# 12ChannelEMG.net
KiCad netlist of a schematic drawn in EAGLE
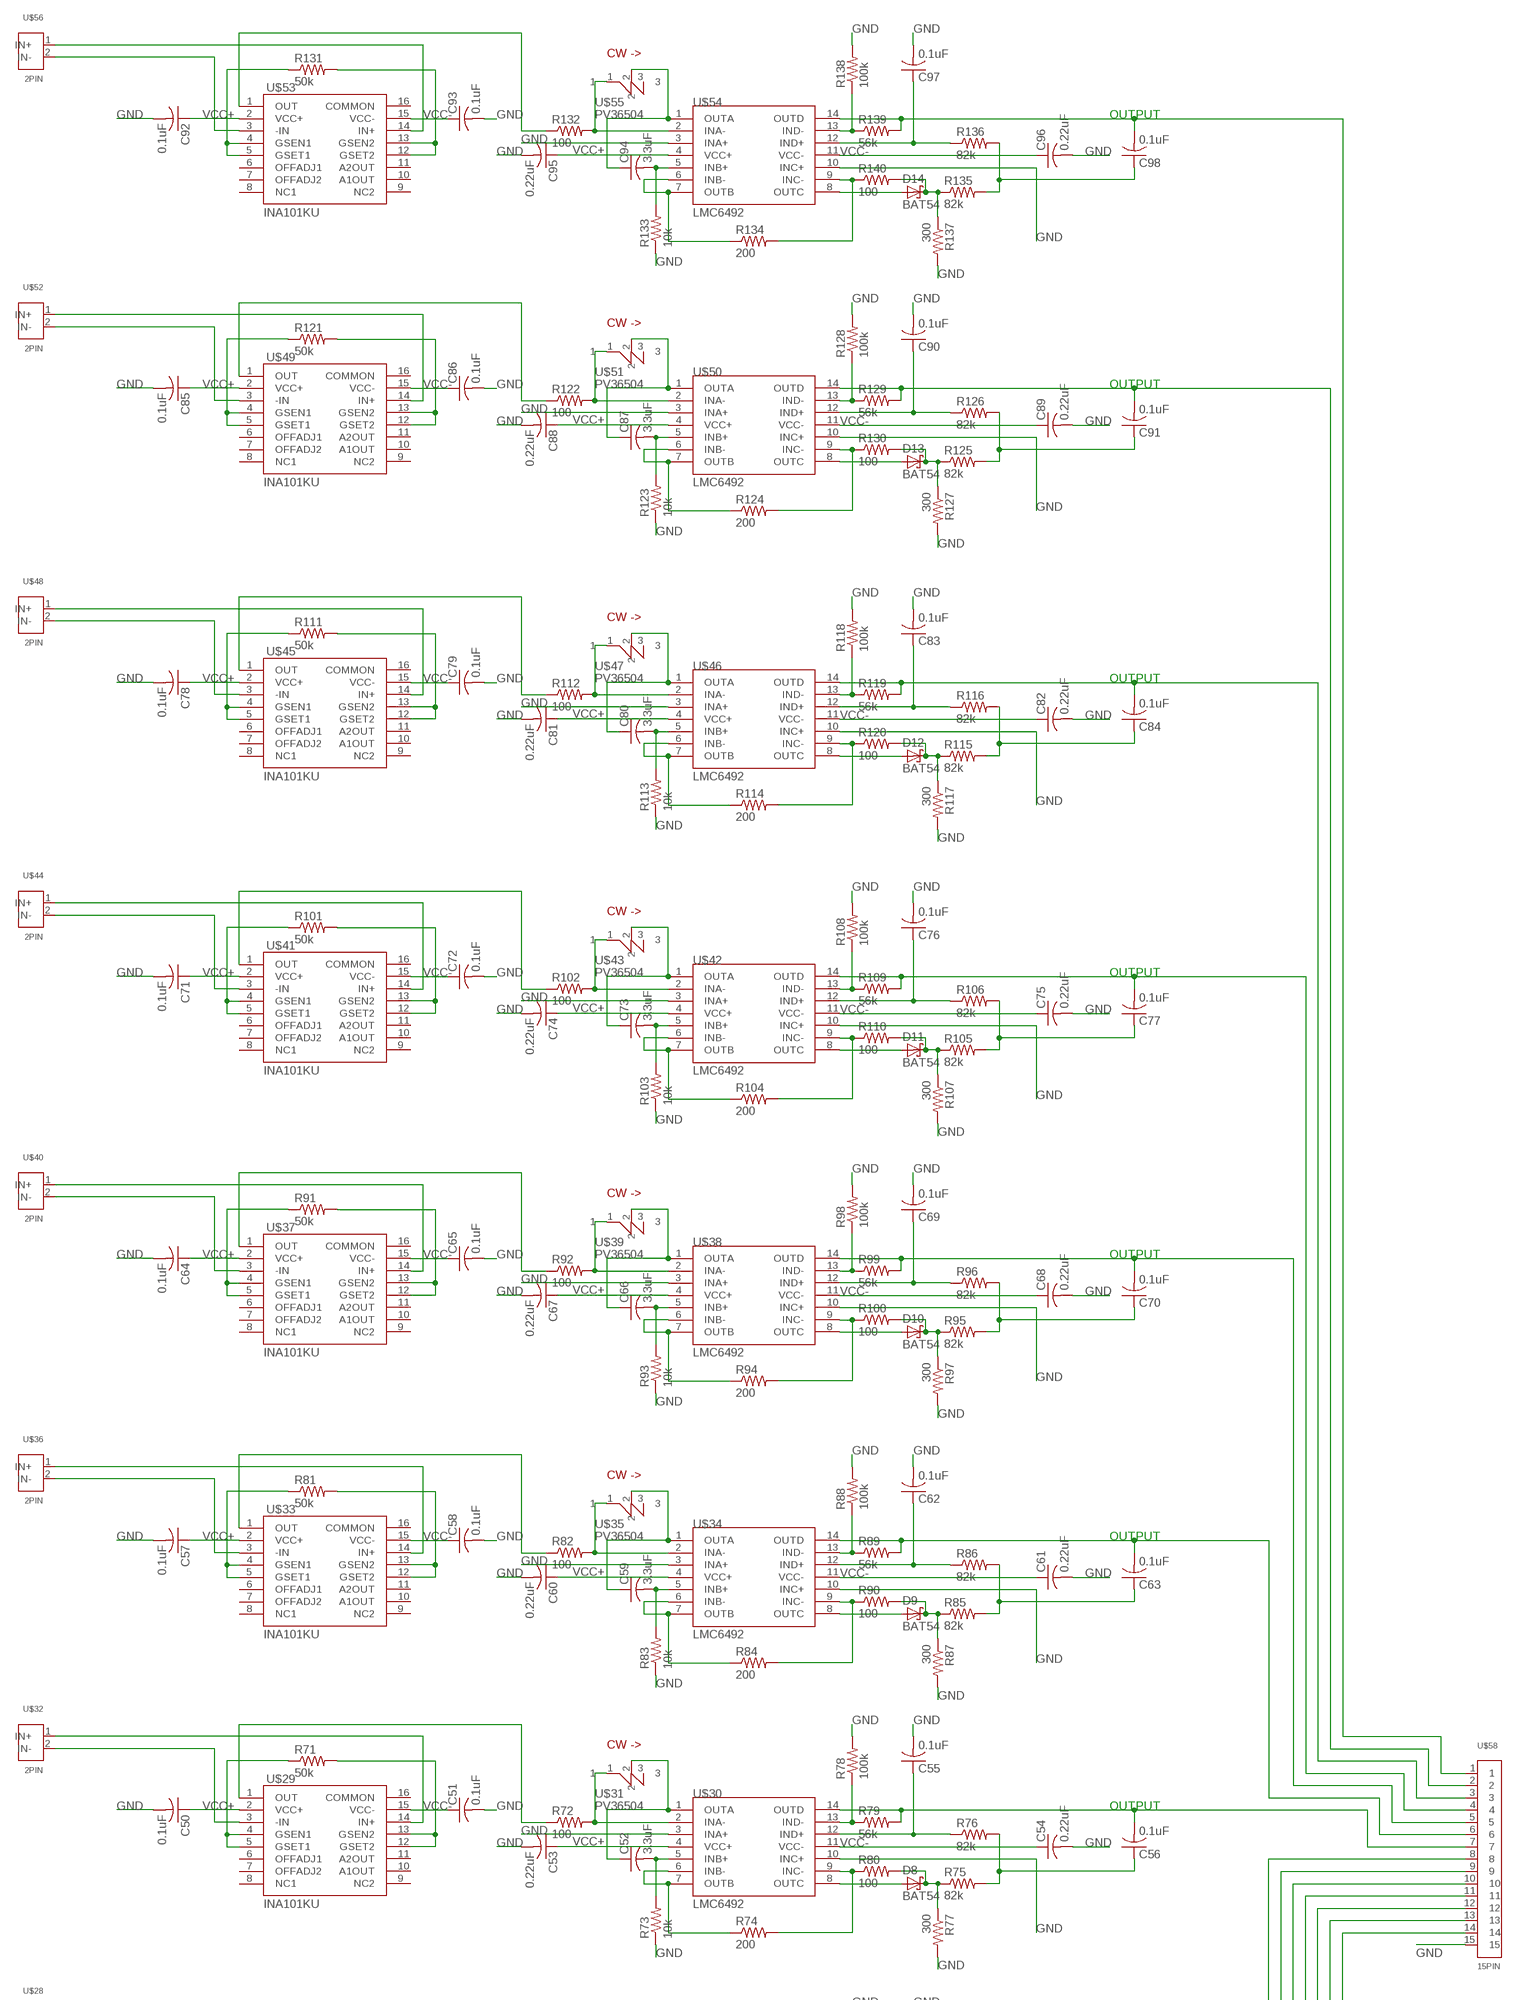
[diagram p0: schematic, sheet 1, part 1 of 2]
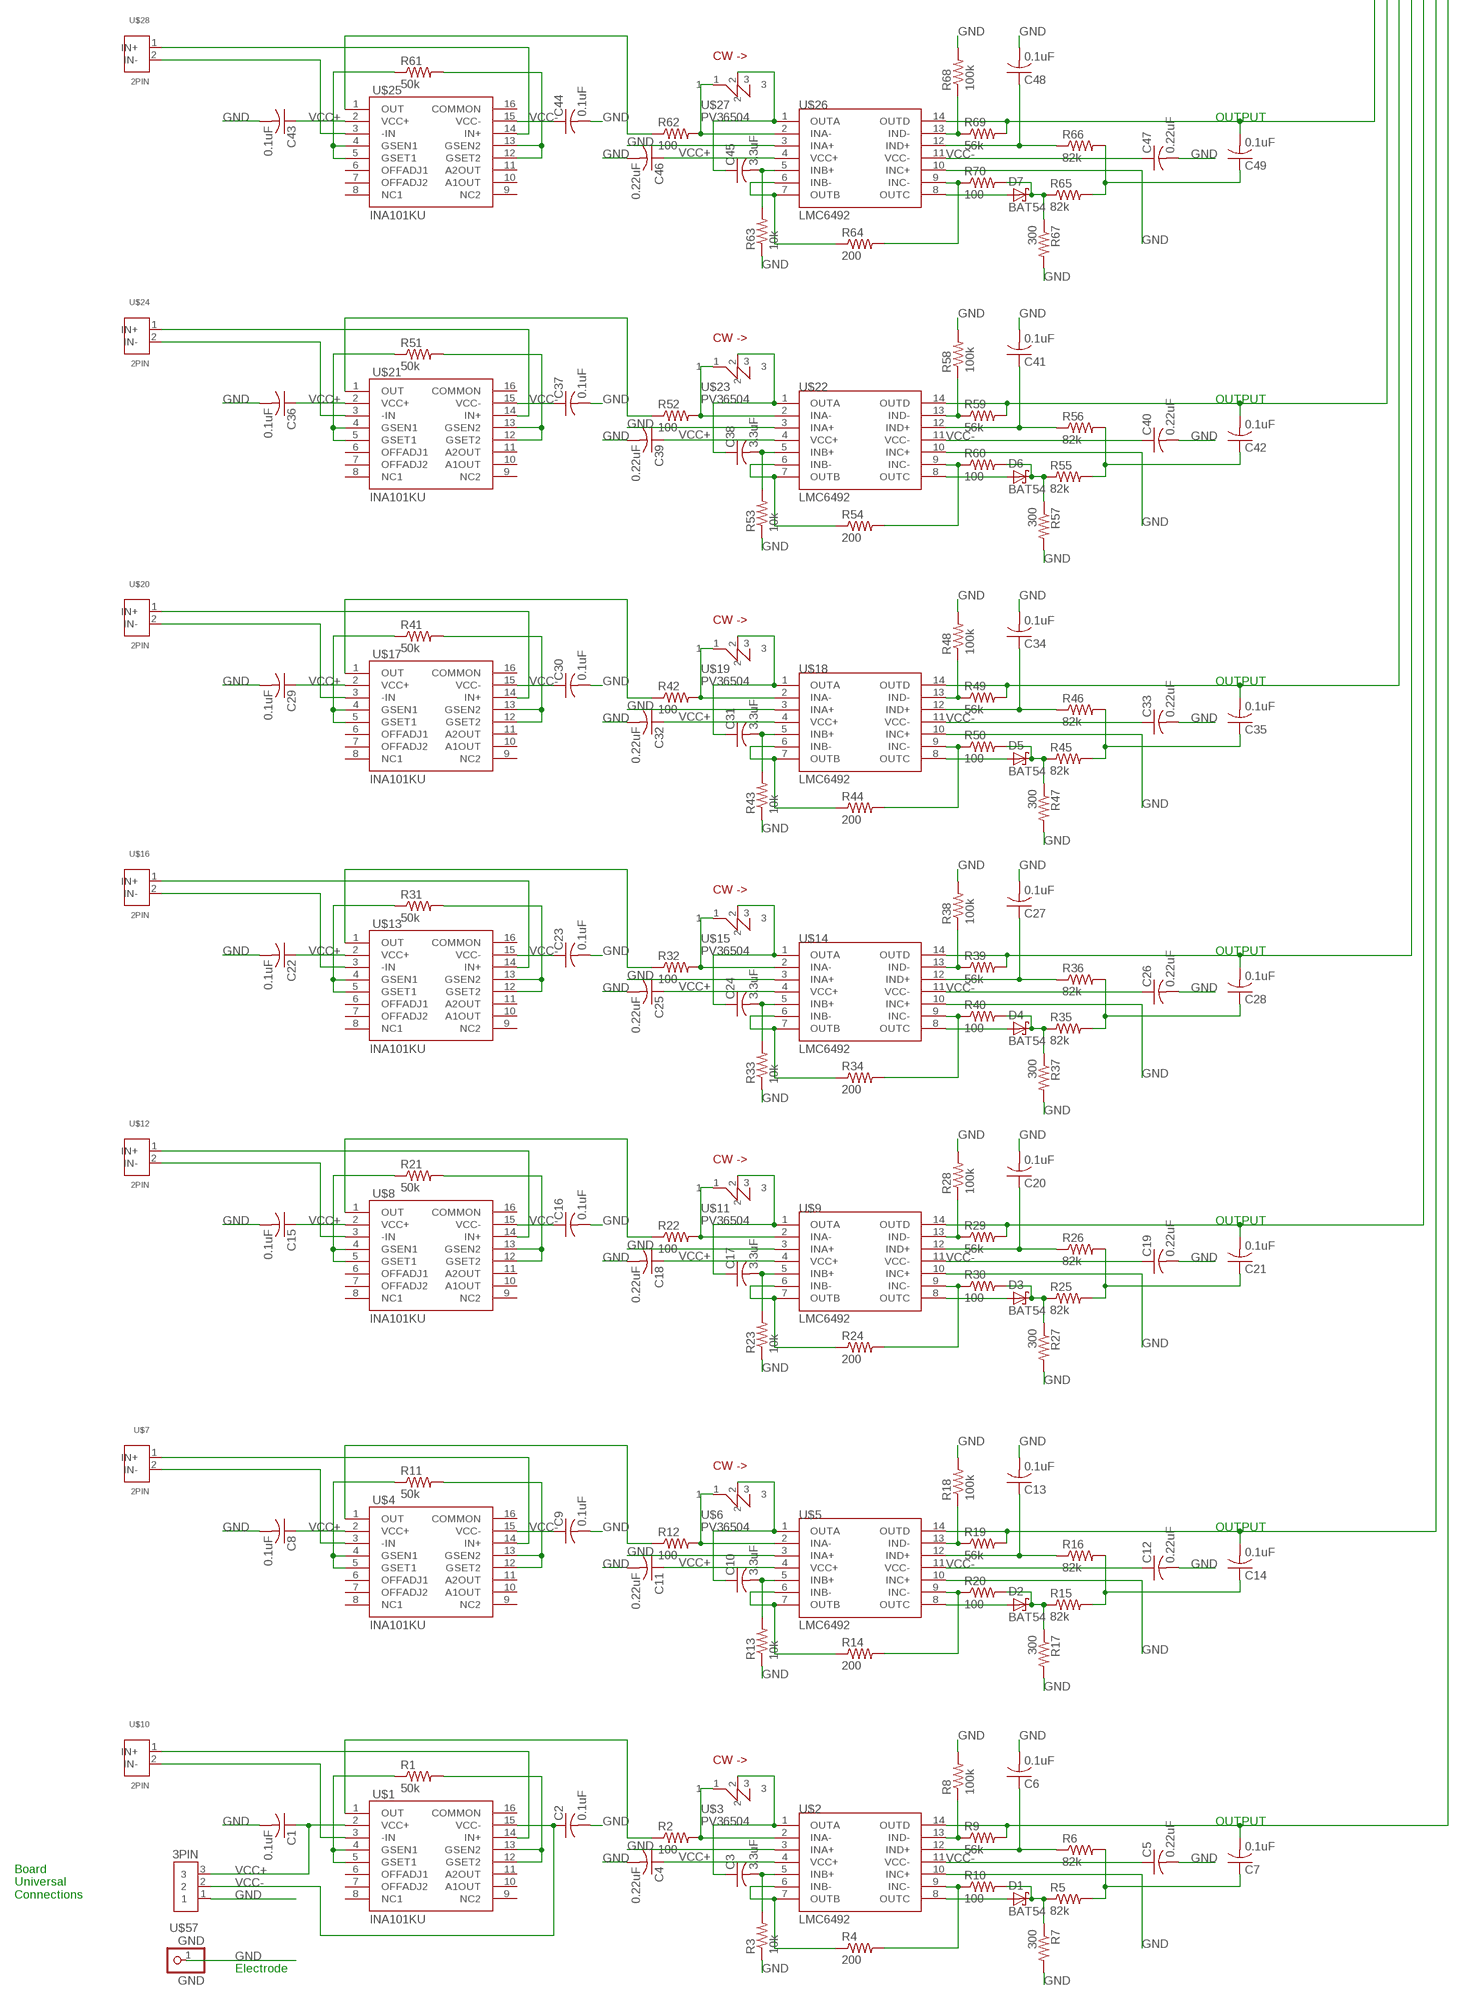
[diagram p1: schematic, sheet 1, part 2 of 2]

(export (version "E")
  (design (tool "Eeschema 10.0.6"))
  (components
    (comp (ref "C1")
      (value "0.1uF")
      (footprint "eagle-import:C1206K")
      (libsource (lib "eagle-import") (part "resistor_C-USC1206K"))
    )
    (comp (ref "C2")
      (value "0.1uF")
      (footprint "eagle-import:C1206K")
      (libsource (lib "eagle-import") (part "resistor_C-USC1206K"))
    )
    (comp (ref "C3")
      (value "3.3uF")
      (footprint "eagle-import:C1206K")
      (libsource (lib "eagle-import") (part "resistor_C-USC1206K"))
    )
    (comp (ref "C4")
      (value "0.22uF")
      (footprint "eagle-import:C0603K")
      (libsource (lib "eagle-import") (part "C-USC0603K"))
    )
    (comp (ref "C5")
      (value "0.22uF")
      (footprint "eagle-import:C0603K")
      (libsource (lib "eagle-import") (part "C-USC0603K"))
    )
    (comp (ref "C6")
      (value "0.1uF")
      (footprint "eagle-import:C1206K")
      (libsource (lib "eagle-import") (part "resistor_C-USC1206K"))
    )
    (comp (ref "C7")
      (value "0.1uF")
      (footprint "eagle-import:C1206K")
      (libsource (lib "eagle-import") (part "resistor_C-USC1206K"))
    )
    (comp (ref "C8")
      (value "0.1uF")
      (footprint "eagle-import:C1206K")
      (libsource (lib "eagle-import") (part "resistor_C-USC1206K"))
    )
    (comp (ref "C9")
      (value "0.1uF")
      (footprint "eagle-import:C1206K")
      (libsource (lib "eagle-import") (part "resistor_C-USC1206K"))
    )
    (comp (ref "C10")
      (value "3.3uF")
      (footprint "eagle-import:C1206K")
      (libsource (lib "eagle-import") (part "resistor_C-USC1206K"))
    )
    (comp (ref "C11")
      (value "0.22uF")
      (footprint "eagle-import:C0603K")
      (libsource (lib "eagle-import") (part "C-USC0603K"))
    )
    (comp (ref "C12")
      (value "0.22uF")
      (footprint "eagle-import:C0603K")
      (libsource (lib "eagle-import") (part "C-USC0603K"))
    )
    (comp (ref "C13")
      (value "0.1uF")
      (footprint "eagle-import:C1206K")
      (libsource (lib "eagle-import") (part "resistor_C-USC1206K"))
    )
    (comp (ref "C14")
      (value "0.1uF")
      (footprint "eagle-import:C1206K")
      (libsource (lib "eagle-import") (part "resistor_C-USC1206K"))
    )
    (comp (ref "C15")
      (value "0.1uF")
      (footprint "eagle-import:C1206K")
      (libsource (lib "eagle-import") (part "resistor_C-USC1206K"))
    )
    (comp (ref "C16")
      (value "0.1uF")
      (footprint "eagle-import:C1206K")
      (libsource (lib "eagle-import") (part "resistor_C-USC1206K"))
    )
    (comp (ref "C17")
      (value "3.3uF")
      (footprint "eagle-import:C1206K")
      (libsource (lib "eagle-import") (part "resistor_C-USC1206K"))
    )
    (comp (ref "C18")
      (value "0.22uF")
      (footprint "eagle-import:C0603K")
      (libsource (lib "eagle-import") (part "C-USC0603K"))
    )
    (comp (ref "C19")
      (value "0.22uF")
      (footprint "eagle-import:C0603K")
      (libsource (lib "eagle-import") (part "C-USC0603K"))
    )
    (comp (ref "C20")
      (value "0.1uF")
      (footprint "eagle-import:C1206K")
      (libsource (lib "eagle-import") (part "resistor_C-USC1206K"))
    )
    (comp (ref "C21")
      (value "0.1uF")
      (footprint "eagle-import:C1206K")
      (libsource (lib "eagle-import") (part "resistor_C-USC1206K"))
    )
    (comp (ref "C22")
      (value "0.1uF")
      (footprint "eagle-import:C1206K")
      (libsource (lib "eagle-import") (part "resistor_C-USC1206K"))
    )
    (comp (ref "C23")
      (value "0.1uF")
      (footprint "eagle-import:C1206K")
      (libsource (lib "eagle-import") (part "resistor_C-USC1206K"))
    )
    (comp (ref "C24")
      (value "3.3uF")
      (footprint "eagle-import:C1206K")
      (libsource (lib "eagle-import") (part "resistor_C-USC1206K"))
    )
    (comp (ref "C25")
      (value "0.22uF")
      (footprint "eagle-import:C0603K")
      (libsource (lib "eagle-import") (part "C-USC0603K"))
    )
    (comp (ref "C26")
      (value "0.22uF")
      (footprint "eagle-import:C0603K")
      (libsource (lib "eagle-import") (part "C-USC0603K"))
    )
    (comp (ref "C27")
      (value "0.1uF")
      (footprint "eagle-import:C1206K")
      (libsource (lib "eagle-import") (part "resistor_C-USC1206K"))
    )
    (comp (ref "C28")
      (value "0.1uF")
      (footprint "eagle-import:C1206K")
      (libsource (lib "eagle-import") (part "resistor_C-USC1206K"))
    )
    (comp (ref "C29")
      (value "0.1uF")
      (footprint "eagle-import:C1206K")
      (libsource (lib "eagle-import") (part "resistor_C-USC1206K"))
    )
    (comp (ref "C30")
      (value "0.1uF")
      (footprint "eagle-import:C1206K")
      (libsource (lib "eagle-import") (part "resistor_C-USC1206K"))
    )
    (comp (ref "C31")
      (value "3.3uF")
      (footprint "eagle-import:C1206K")
      (libsource (lib "eagle-import") (part "resistor_C-USC1206K"))
    )
    (comp (ref "C32")
      (value "0.22uF")
      (footprint "eagle-import:C0603K")
      (libsource (lib "eagle-import") (part "C-USC0603K"))
    )
    (comp (ref "C33")
      (value "0.22uF")
      (footprint "eagle-import:C0603K")
      (libsource (lib "eagle-import") (part "C-USC0603K"))
    )
    (comp (ref "C34")
      (value "0.1uF")
      (footprint "eagle-import:C1206K")
      (libsource (lib "eagle-import") (part "resistor_C-USC1206K"))
    )
    (comp (ref "C35")
      (value "0.1uF")
      (footprint "eagle-import:C1206K")
      (libsource (lib "eagle-import") (part "resistor_C-USC1206K"))
    )
    (comp (ref "C36")
      (value "0.1uF")
      (footprint "eagle-import:C1206K")
      (libsource (lib "eagle-import") (part "resistor_C-USC1206K"))
    )
    (comp (ref "C37")
      (value "0.1uF")
      (footprint "eagle-import:C1206K")
      (libsource (lib "eagle-import") (part "resistor_C-USC1206K"))
    )
    (comp (ref "C38")
      (value "3.3uF")
      (footprint "eagle-import:C1206K")
      (libsource (lib "eagle-import") (part "resistor_C-USC1206K"))
    )
    (comp (ref "C39")
      (value "0.22uF")
      (footprint "eagle-import:C0603K")
      (libsource (lib "eagle-import") (part "C-USC0603K"))
    )
    (comp (ref "C40")
      (value "0.22uF")
      (footprint "eagle-import:C0603K")
      (libsource (lib "eagle-import") (part "C-USC0603K"))
    )
    (comp (ref "C41")
      (value "0.1uF")
      (footprint "eagle-import:C1206K")
      (libsource (lib "eagle-import") (part "resistor_C-USC1206K"))
    )
    (comp (ref "C42")
      (value "0.1uF")
      (footprint "eagle-import:C1206K")
      (libsource (lib "eagle-import") (part "resistor_C-USC1206K"))
    )
    (comp (ref "C43")
      (value "0.1uF")
      (footprint "eagle-import:C1206K")
      (libsource (lib "eagle-import") (part "resistor_C-USC1206K"))
    )
    (comp (ref "C44")
      (value "0.1uF")
      (footprint "eagle-import:C1206K")
      (libsource (lib "eagle-import") (part "resistor_C-USC1206K"))
    )
    (comp (ref "C45")
      (value "3.3uF")
      (footprint "eagle-import:C1206K")
      (libsource (lib "eagle-import") (part "resistor_C-USC1206K"))
    )
    (comp (ref "C46")
      (value "0.22uF")
      (footprint "eagle-import:C0603K")
      (libsource (lib "eagle-import") (part "C-USC0603K"))
    )
    (comp (ref "C47")
      (value "0.22uF")
      (footprint "eagle-import:C0603K")
      (libsource (lib "eagle-import") (part "C-USC0603K"))
    )
    (comp (ref "C48")
      (value "0.1uF")
      (footprint "eagle-import:C1206K")
      (libsource (lib "eagle-import") (part "resistor_C-USC1206K"))
    )
    (comp (ref "C49")
      (value "0.1uF")
      (footprint "eagle-import:C1206K")
      (libsource (lib "eagle-import") (part "resistor_C-USC1206K"))
    )
    (comp (ref "C50")
      (value "0.1uF")
      (footprint "eagle-import:C1206K")
      (libsource (lib "eagle-import") (part "resistor_C-USC1206K"))
    )
    (comp (ref "C51")
      (value "0.1uF")
      (footprint "eagle-import:C1206K")
      (libsource (lib "eagle-import") (part "resistor_C-USC1206K"))
    )
    (comp (ref "C52")
      (value "3.3uF")
      (footprint "eagle-import:C1206K")
      (libsource (lib "eagle-import") (part "resistor_C-USC1206K"))
    )
    (comp (ref "C53")
      (value "0.22uF")
      (footprint "eagle-import:C0603K")
      (libsource (lib "eagle-import") (part "C-USC0603K"))
    )
    (comp (ref "C54")
      (value "0.22uF")
      (footprint "eagle-import:C0603K")
      (libsource (lib "eagle-import") (part "C-USC0603K"))
    )
    (comp (ref "C55")
      (value "0.1uF")
      (footprint "eagle-import:C1206K")
      (libsource (lib "eagle-import") (part "resistor_C-USC1206K"))
    )
    (comp (ref "C56")
      (value "0.1uF")
      (footprint "eagle-import:C1206K")
      (libsource (lib "eagle-import") (part "resistor_C-USC1206K"))
    )
    (comp (ref "C57")
      (value "0.1uF")
      (footprint "eagle-import:C1206K")
      (libsource (lib "eagle-import") (part "resistor_C-USC1206K"))
    )
    (comp (ref "C58")
      (value "0.1uF")
      (footprint "eagle-import:C1206K")
      (libsource (lib "eagle-import") (part "resistor_C-USC1206K"))
    )
    (comp (ref "C59")
      (value "3.3uF")
      (footprint "eagle-import:C1206K")
      (libsource (lib "eagle-import") (part "resistor_C-USC1206K"))
    )
    (comp (ref "C60")
      (value "0.22uF")
      (footprint "eagle-import:C0603K")
      (libsource (lib "eagle-import") (part "C-USC0603K"))
    )
    (comp (ref "C61")
      (value "0.22uF")
      (footprint "eagle-import:C0603K")
      (libsource (lib "eagle-import") (part "C-USC0603K"))
    )
    (comp (ref "C62")
      (value "0.1uF")
      (footprint "eagle-import:C1206K")
      (libsource (lib "eagle-import") (part "resistor_C-USC1206K"))
    )
    (comp (ref "C63")
      (value "0.1uF")
      (footprint "eagle-import:C1206K")
      (libsource (lib "eagle-import") (part "resistor_C-USC1206K"))
    )
    (comp (ref "C64")
      (value "0.1uF")
      (footprint "eagle-import:C1206K")
      (libsource (lib "eagle-import") (part "resistor_C-USC1206K"))
    )
    (comp (ref "C65")
      (value "0.1uF")
      (footprint "eagle-import:C1206K")
      (libsource (lib "eagle-import") (part "resistor_C-USC1206K"))
    )
    (comp (ref "C66")
      (value "3.3uF")
      (footprint "eagle-import:C1206K")
      (libsource (lib "eagle-import") (part "resistor_C-USC1206K"))
    )
    (comp (ref "C67")
      (value "0.22uF")
      (footprint "eagle-import:C0603K")
      (libsource (lib "eagle-import") (part "C-USC0603K"))
    )
    (comp (ref "C68")
      (value "0.22uF")
      (footprint "eagle-import:C0603K")
      (libsource (lib "eagle-import") (part "C-USC0603K"))
    )
    (comp (ref "C69")
      (value "0.1uF")
      (footprint "eagle-import:C1206K")
      (libsource (lib "eagle-import") (part "resistor_C-USC1206K"))
    )
    (comp (ref "C70")
      (value "0.1uF")
      (footprint "eagle-import:C1206K")
      (libsource (lib "eagle-import") (part "resistor_C-USC1206K"))
    )
    (comp (ref "C71")
      (value "0.1uF")
      (footprint "eagle-import:C1206K")
      (libsource (lib "eagle-import") (part "resistor_C-USC1206K"))
    )
    (comp (ref "C72")
      (value "0.1uF")
      (footprint "eagle-import:C1206K")
      (libsource (lib "eagle-import") (part "resistor_C-USC1206K"))
    )
    (comp (ref "C73")
      (value "3.3uF")
      (footprint "eagle-import:C1206K")
      (libsource (lib "eagle-import") (part "resistor_C-USC1206K"))
    )
    (comp (ref "C74")
      (value "0.22uF")
      (footprint "eagle-import:C0603K")
      (libsource (lib "eagle-import") (part "C-USC0603K"))
    )
    (comp (ref "C75")
      (value "0.22uF")
      (footprint "eagle-import:C0603K")
      (libsource (lib "eagle-import") (part "C-USC0603K"))
    )
    (comp (ref "C76")
      (value "0.1uF")
      (footprint "eagle-import:C1206K")
      (libsource (lib "eagle-import") (part "resistor_C-USC1206K"))
    )
    (comp (ref "C77")
      (value "0.1uF")
      (footprint "eagle-import:C1206K")
      (libsource (lib "eagle-import") (part "resistor_C-USC1206K"))
    )
    (comp (ref "C78")
      (value "0.1uF")
      (footprint "eagle-import:C1206K")
      (libsource (lib "eagle-import") (part "resistor_C-USC1206K"))
    )
    (comp (ref "C79")
      (value "0.1uF")
      (footprint "eagle-import:C1206K")
      (libsource (lib "eagle-import") (part "resistor_C-USC1206K"))
    )
    (comp (ref "C80")
      (value "3.3uF")
      (footprint "eagle-import:C1206K")
      (libsource (lib "eagle-import") (part "resistor_C-USC1206K"))
    )
    (comp (ref "C81")
      (value "0.22uF")
      (footprint "eagle-import:C0603K")
      (libsource (lib "eagle-import") (part "C-USC0603K"))
    )
    (comp (ref "C82")
      (value "0.22uF")
      (footprint "eagle-import:C0603K")
      (libsource (lib "eagle-import") (part "C-USC0603K"))
    )
    (comp (ref "C83")
      (value "0.1uF")
      (footprint "eagle-import:C1206K")
      (libsource (lib "eagle-import") (part "resistor_C-USC1206K"))
    )
    (comp (ref "C84")
      (value "0.1uF")
      (footprint "eagle-import:C1206K")
      (libsource (lib "eagle-import") (part "resistor_C-USC1206K"))
    )
    (comp (ref "C85")
      (value "0.1uF")
      (footprint "eagle-import:C1206K")
      (libsource (lib "eagle-import") (part "resistor_C-USC1206K"))
    )
    (comp (ref "C86")
      (value "0.1uF")
      (footprint "eagle-import:C1206K")
      (libsource (lib "eagle-import") (part "resistor_C-USC1206K"))
    )
    (comp (ref "C87")
      (value "3.3uF")
      (footprint "eagle-import:C1206K")
      (libsource (lib "eagle-import") (part "resistor_C-USC1206K"))
    )
    (comp (ref "C88")
      (value "0.22uF")
      (footprint "eagle-import:C0603K")
      (libsource (lib "eagle-import") (part "C-USC0603K"))
    )
    (comp (ref "C89")
      (value "0.22uF")
      (footprint "eagle-import:C0603K")
      (libsource (lib "eagle-import") (part "C-USC0603K"))
    )
    (comp (ref "C90")
      (value "0.1uF")
      (footprint "eagle-import:C1206K")
      (libsource (lib "eagle-import") (part "resistor_C-USC1206K"))
    )
    (comp (ref "C91")
      (value "0.1uF")
      (footprint "eagle-import:C1206K")
      (libsource (lib "eagle-import") (part "resistor_C-USC1206K"))
    )
    (comp (ref "C92")
      (value "0.1uF")
      (footprint "eagle-import:C1206K")
      (libsource (lib "eagle-import") (part "resistor_C-USC1206K"))
    )
    (comp (ref "C93")
      (value "0.1uF")
      (footprint "eagle-import:C1206K")
      (libsource (lib "eagle-import") (part "resistor_C-USC1206K"))
    )
    (comp (ref "C94")
      (value "3.3uF")
      (footprint "eagle-import:C1206K")
      (libsource (lib "eagle-import") (part "resistor_C-USC1206K"))
    )
    (comp (ref "C95")
      (value "0.22uF")
      (footprint "eagle-import:C0603K")
      (libsource (lib "eagle-import") (part "C-USC0603K"))
    )
    (comp (ref "C96")
      (value "0.22uF")
      (footprint "eagle-import:C0603K")
      (libsource (lib "eagle-import") (part "C-USC0603K"))
    )
    (comp (ref "C97")
      (value "0.1uF")
      (footprint "eagle-import:C1206K")
      (libsource (lib "eagle-import") (part "resistor_C-USC1206K"))
    )
    (comp (ref "C98")
      (value "0.1uF")
      (footprint "eagle-import:C1206K")
      (libsource (lib "eagle-import") (part "resistor_C-USC1206K"))
    )
    (comp (ref "D1")
      (value "BAT54")
      (footprint "eagle-import:SOT23")
      (libsource (lib "eagle-import") (part "BAT54"))
    )
    (comp (ref "D2")
      (value "BAT54")
      (footprint "eagle-import:SOT23")
      (libsource (lib "eagle-import") (part "BAT54"))
    )
    (comp (ref "D3")
      (value "BAT54")
      (footprint "eagle-import:SOT23")
      (libsource (lib "eagle-import") (part "BAT54"))
    )
    (comp (ref "D4")
      (value "BAT54")
      (footprint "eagle-import:SOT23")
      (libsource (lib "eagle-import") (part "BAT54"))
    )
    (comp (ref "D5")
      (value "BAT54")
      (footprint "eagle-import:SOT23")
      (libsource (lib "eagle-import") (part "BAT54"))
    )
    (comp (ref "D6")
      (value "BAT54")
      (footprint "eagle-import:SOT23")
      (libsource (lib "eagle-import") (part "BAT54"))
    )
    (comp (ref "D7")
      (value "BAT54")
      (footprint "eagle-import:SOT23")
      (libsource (lib "eagle-import") (part "BAT54"))
    )
    (comp (ref "D8")
      (value "BAT54")
      (footprint "eagle-import:SOT23")
      (libsource (lib "eagle-import") (part "BAT54"))
    )
    (comp (ref "D9")
      (value "BAT54")
      (footprint "eagle-import:SOT23")
      (libsource (lib "eagle-import") (part "BAT54"))
    )
    (comp (ref "D10")
      (value "BAT54")
      (footprint "eagle-import:SOT23")
      (libsource (lib "eagle-import") (part "BAT54"))
    )
    (comp (ref "D11")
      (value "BAT54")
      (footprint "eagle-import:SOT23")
      (libsource (lib "eagle-import") (part "BAT54"))
    )
    (comp (ref "D12")
      (value "BAT54")
      (footprint "eagle-import:SOT23")
      (libsource (lib "eagle-import") (part "BAT54"))
    )
    (comp (ref "D13")
      (value "BAT54")
      (footprint "eagle-import:SOT23")
      (libsource (lib "eagle-import") (part "BAT54"))
    )
    (comp (ref "D14")
      (value "BAT54")
      (footprint "eagle-import:SOT23")
      (libsource (lib "eagle-import") (part "BAT54"))
    )
    (comp (ref "GND")
      (value "GND")
      (footprint "eagle-import:1X01")
      (libsource (lib "eagle-import") (part "PINHD-1X1"))
    )
    (comp (ref "R1")
      (value "50k")
      (footprint "eagle-import:R0805")
      (libsource (lib "eagle-import") (part "R-US_R0805"))
    )
    (comp (ref "R2")
      (value "100")
      (footprint "eagle-import:R0603")
      (libsource (lib "eagle-import") (part "resistor_R-US_R0603"))
    )
    (comp (ref "R3")
      (value "10k")
      (footprint "eagle-import:R0603")
      (libsource (lib "eagle-import") (part "R-US_R0603"))
    )
    (comp (ref "R4")
      (value "200")
      (footprint "eagle-import:R0603")
      (libsource (lib "eagle-import") (part "R-US_R0603"))
    )
    (comp (ref "R5")
      (value "82k")
      (footprint "eagle-import:R0603")
      (libsource (lib "eagle-import") (part "resistor_R-US_R0603"))
    )
    (comp (ref "R6")
      (value "82k")
      (footprint "eagle-import:R0603")
      (libsource (lib "eagle-import") (part "resistor_R-US_R0603"))
    )
    (comp (ref "R7")
      (value "300")
      (footprint "eagle-import:R0603")
      (libsource (lib "eagle-import") (part "resistor_R-US_R0603"))
    )
    (comp (ref "R8")
      (value "100k")
      (footprint "eagle-import:R0603")
      (libsource (lib "eagle-import") (part "resistor_R-US_R0603"))
    )
    (comp (ref "R9")
      (value "56k")
      (footprint "eagle-import:R0603")
      (libsource (lib "eagle-import") (part "resistor_R-US_R0603"))
    )
    (comp (ref "R10")
      (value "100")
      (footprint "eagle-import:R0603")
      (libsource (lib "eagle-import") (part "resistor_R-US_R0603"))
    )
    (comp (ref "R11")
      (value "50k")
      (footprint "eagle-import:R0805")
      (libsource (lib "eagle-import") (part "R-US_R0805"))
    )
    (comp (ref "R12")
      (value "100")
      (footprint "eagle-import:R0603")
      (libsource (lib "eagle-import") (part "resistor_R-US_R0603"))
    )
    (comp (ref "R13")
      (value "10k")
      (footprint "eagle-import:R0603")
      (libsource (lib "eagle-import") (part "R-US_R0603"))
    )
    (comp (ref "R14")
      (value "200")
      (footprint "eagle-import:R0603")
      (libsource (lib "eagle-import") (part "R-US_R0603"))
    )
    (comp (ref "R15")
      (value "82k")
      (footprint "eagle-import:R0603")
      (libsource (lib "eagle-import") (part "resistor_R-US_R0603"))
    )
    (comp (ref "R16")
      (value "82k")
      (footprint "eagle-import:R0603")
      (libsource (lib "eagle-import") (part "resistor_R-US_R0603"))
    )
    (comp (ref "R17")
      (value "300")
      (footprint "eagle-import:R0603")
      (libsource (lib "eagle-import") (part "resistor_R-US_R0603"))
    )
    (comp (ref "R18")
      (value "100k")
      (footprint "eagle-import:R0603")
      (libsource (lib "eagle-import") (part "resistor_R-US_R0603"))
    )
    (comp (ref "R19")
      (value "56k")
      (footprint "eagle-import:R0603")
      (libsource (lib "eagle-import") (part "resistor_R-US_R0603"))
    )
    (comp (ref "R20")
      (value "100")
      (footprint "eagle-import:R0603")
      (libsource (lib "eagle-import") (part "resistor_R-US_R0603"))
    )
    (comp (ref "R21")
      (value "50k")
      (footprint "eagle-import:R0805")
      (libsource (lib "eagle-import") (part "R-US_R0805"))
    )
    (comp (ref "R22")
      (value "100")
      (footprint "eagle-import:R0603")
      (libsource (lib "eagle-import") (part "resistor_R-US_R0603"))
    )
    (comp (ref "R23")
      (value "10k")
      (footprint "eagle-import:R0603")
      (libsource (lib "eagle-import") (part "R-US_R0603"))
    )
    (comp (ref "R24")
      (value "200")
      (footprint "eagle-import:R0603")
      (libsource (lib "eagle-import") (part "R-US_R0603"))
    )
    (comp (ref "R25")
      (value "82k")
      (footprint "eagle-import:R0603")
      (libsource (lib "eagle-import") (part "resistor_R-US_R0603"))
    )
    (comp (ref "R26")
      (value "82k")
      (footprint "eagle-import:R0603")
      (libsource (lib "eagle-import") (part "resistor_R-US_R0603"))
    )
    (comp (ref "R27")
      (value "300")
      (footprint "eagle-import:R0603")
      (libsource (lib "eagle-import") (part "resistor_R-US_R0603"))
    )
    (comp (ref "R28")
      (value "100k")
      (footprint "eagle-import:R0603")
      (libsource (lib "eagle-import") (part "resistor_R-US_R0603"))
    )
    (comp (ref "R29")
      (value "56k")
      (footprint "eagle-import:R0603")
      (libsource (lib "eagle-import") (part "resistor_R-US_R0603"))
    )
    (comp (ref "R30")
      (value "100")
      (footprint "eagle-import:R0603")
      (libsource (lib "eagle-import") (part "resistor_R-US_R0603"))
    )
    (comp (ref "R31")
      (value "50k")
      (footprint "eagle-import:R0805")
      (libsource (lib "eagle-import") (part "R-US_R0805"))
    )
    (comp (ref "R32")
      (value "100")
      (footprint "eagle-import:R0603")
      (libsource (lib "eagle-import") (part "resistor_R-US_R0603"))
    )
    (comp (ref "R33")
      (value "10k")
      (footprint "eagle-import:R0603")
      (libsource (lib "eagle-import") (part "R-US_R0603"))
    )
    (comp (ref "R34")
      (value "200")
      (footprint "eagle-import:R0603")
      (libsource (lib "eagle-import") (part "R-US_R0603"))
    )
    (comp (ref "R35")
      (value "82k")
      (footprint "eagle-import:R0603")
      (libsource (lib "eagle-import") (part "resistor_R-US_R0603"))
    )
    (comp (ref "R36")
      (value "82k")
      (footprint "eagle-import:R0603")
      (libsource (lib "eagle-import") (part "resistor_R-US_R0603"))
    )
    (comp (ref "R37")
      (value "300")
      (footprint "eagle-import:R0603")
      (libsource (lib "eagle-import") (part "resistor_R-US_R0603"))
    )
    (comp (ref "R38")
      (value "100k")
      (footprint "eagle-import:R0603")
      (libsource (lib "eagle-import") (part "resistor_R-US_R0603"))
    )
    (comp (ref "R39")
      (value "56k")
      (footprint "eagle-import:R0603")
      (libsource (lib "eagle-import") (part "resistor_R-US_R0603"))
    )
    (comp (ref "R40")
      (value "100")
      (footprint "eagle-import:R0603")
      (libsource (lib "eagle-import") (part "resistor_R-US_R0603"))
    )
    (comp (ref "R41")
      (value "50k")
      (footprint "eagle-import:R0805")
      (libsource (lib "eagle-import") (part "R-US_R0805"))
    )
    (comp (ref "R42")
      (value "100")
      (footprint "eagle-import:R0603")
      (libsource (lib "eagle-import") (part "resistor_R-US_R0603"))
    )
    (comp (ref "R43")
      (value "10k")
      (footprint "eagle-import:R0603")
      (libsource (lib "eagle-import") (part "R-US_R0603"))
    )
    (comp (ref "R44")
      (value "200")
      (footprint "eagle-import:R0603")
      (libsource (lib "eagle-import") (part "R-US_R0603"))
    )
    (comp (ref "R45")
      (value "82k")
      (footprint "eagle-import:R0603")
      (libsource (lib "eagle-import") (part "resistor_R-US_R0603"))
    )
    (comp (ref "R46")
      (value "82k")
      (footprint "eagle-import:R0603")
      (libsource (lib "eagle-import") (part "resistor_R-US_R0603"))
    )
    (comp (ref "R47")
      (value "300")
      (footprint "eagle-import:R0603")
      (libsource (lib "eagle-import") (part "resistor_R-US_R0603"))
    )
    (comp (ref "R48")
      (value "100k")
      (footprint "eagle-import:R0603")
      (libsource (lib "eagle-import") (part "resistor_R-US_R0603"))
    )
    (comp (ref "R49")
      (value "56k")
      (footprint "eagle-import:R0603")
      (libsource (lib "eagle-import") (part "resistor_R-US_R0603"))
    )
    (comp (ref "R50")
      (value "100")
      (footprint "eagle-import:R0603")
      (libsource (lib "eagle-import") (part "resistor_R-US_R0603"))
    )
    (comp (ref "R51")
      (value "50k")
      (footprint "eagle-import:R0805")
      (libsource (lib "eagle-import") (part "R-US_R0805"))
    )
    (comp (ref "R52")
      (value "100")
      (footprint "eagle-import:R0603")
      (libsource (lib "eagle-import") (part "resistor_R-US_R0603"))
    )
    (comp (ref "R53")
      (value "10k")
      (footprint "eagle-import:R0603")
      (libsource (lib "eagle-import") (part "R-US_R0603"))
    )
    (comp (ref "R54")
      (value "200")
      (footprint "eagle-import:R0603")
      (libsource (lib "eagle-import") (part "R-US_R0603"))
    )
    (comp (ref "R55")
      (value "82k")
      (footprint "eagle-import:R0603")
      (libsource (lib "eagle-import") (part "resistor_R-US_R0603"))
    )
    (comp (ref "R56")
      (value "82k")
      (footprint "eagle-import:R0603")
      (libsource (lib "eagle-import") (part "resistor_R-US_R0603"))
    )
    (comp (ref "R57")
      (value "300")
      (footprint "eagle-import:R0603")
      (libsource (lib "eagle-import") (part "resistor_R-US_R0603"))
    )
    (comp (ref "R58")
      (value "100k")
      (footprint "eagle-import:R0603")
      (libsource (lib "eagle-import") (part "resistor_R-US_R0603"))
    )
    (comp (ref "R59")
      (value "56k")
      (footprint "eagle-import:R0603")
      (libsource (lib "eagle-import") (part "resistor_R-US_R0603"))
    )
    (comp (ref "R60")
      (value "100")
      (footprint "eagle-import:R0603")
      (libsource (lib "eagle-import") (part "resistor_R-US_R0603"))
    )
    (comp (ref "R61")
      (value "50k")
      (footprint "eagle-import:R0805")
      (libsource (lib "eagle-import") (part "R-US_R0805"))
    )
    (comp (ref "R62")
      (value "100")
      (footprint "eagle-import:R0603")
      (libsource (lib "eagle-import") (part "resistor_R-US_R0603"))
    )
    (comp (ref "R63")
      (value "10k")
      (footprint "eagle-import:R0603")
      (libsource (lib "eagle-import") (part "R-US_R0603"))
    )
    (comp (ref "R64")
      (value "200")
      (footprint "eagle-import:R0603")
      (libsource (lib "eagle-import") (part "R-US_R0603"))
    )
    (comp (ref "R65")
      (value "82k")
      (footprint "eagle-import:R0603")
      (libsource (lib "eagle-import") (part "resistor_R-US_R0603"))
    )
    (comp (ref "R66")
      (value "82k")
      (footprint "eagle-import:R0603")
      (libsource (lib "eagle-import") (part "resistor_R-US_R0603"))
    )
    (comp (ref "R67")
      (value "300")
      (footprint "eagle-import:R0603")
      (libsource (lib "eagle-import") (part "resistor_R-US_R0603"))
    )
    (comp (ref "R68")
      (value "100k")
      (footprint "eagle-import:R0603")
      (libsource (lib "eagle-import") (part "resistor_R-US_R0603"))
    )
    (comp (ref "R69")
      (value "56k")
      (footprint "eagle-import:R0603")
      (libsource (lib "eagle-import") (part "resistor_R-US_R0603"))
    )
    (comp (ref "R70")
      (value "100")
      (footprint "eagle-import:R0603")
      (libsource (lib "eagle-import") (part "resistor_R-US_R0603"))
    )
    (comp (ref "R71")
      (value "50k")
      (footprint "eagle-import:R0805")
      (libsource (lib "eagle-import") (part "R-US_R0805"))
    )
    (comp (ref "R72")
      (value "100")
      (footprint "eagle-import:R0603")
      (libsource (lib "eagle-import") (part "resistor_R-US_R0603"))
    )
    (comp (ref "R73")
      (value "10k")
      (footprint "eagle-import:R0603")
      (libsource (lib "eagle-import") (part "R-US_R0603"))
    )
    (comp (ref "R74")
      (value "200")
      (footprint "eagle-import:R0603")
      (libsource (lib "eagle-import") (part "R-US_R0603"))
    )
    (comp (ref "R75")
      (value "82k")
      (footprint "eagle-import:R0603")
      (libsource (lib "eagle-import") (part "resistor_R-US_R0603"))
    )
    (comp (ref "R76")
      (value "82k")
      (footprint "eagle-import:R0603")
      (libsource (lib "eagle-import") (part "resistor_R-US_R0603"))
    )
    (comp (ref "R77")
      (value "300")
      (footprint "eagle-import:R0603")
      (libsource (lib "eagle-import") (part "resistor_R-US_R0603"))
    )
    (comp (ref "R78")
      (value "100k")
      (footprint "eagle-import:R0603")
      (libsource (lib "eagle-import") (part "resistor_R-US_R0603"))
    )
    (comp (ref "R79")
      (value "56k")
      (footprint "eagle-import:R0603")
      (libsource (lib "eagle-import") (part "resistor_R-US_R0603"))
    )
    (comp (ref "R80")
      (value "100")
      (footprint "eagle-import:R0603")
      (libsource (lib "eagle-import") (part "resistor_R-US_R0603"))
    )
    (comp (ref "R81")
      (value "50k")
      (footprint "eagle-import:R0805")
      (libsource (lib "eagle-import") (part "R-US_R0805"))
    )
    (comp (ref "R82")
      (value "100")
      (footprint "eagle-import:R0603")
      (libsource (lib "eagle-import") (part "resistor_R-US_R0603"))
    )
    (comp (ref "R83")
      (value "10k")
      (footprint "eagle-import:R0603")
      (libsource (lib "eagle-import") (part "R-US_R0603"))
    )
    (comp (ref "R84")
      (value "200")
      (footprint "eagle-import:R0603")
      (libsource (lib "eagle-import") (part "R-US_R0603"))
    )
    (comp (ref "R85")
      (value "82k")
      (footprint "eagle-import:R0603")
      (libsource (lib "eagle-import") (part "resistor_R-US_R0603"))
    )
    (comp (ref "R86")
      (value "82k")
      (footprint "eagle-import:R0603")
      (libsource (lib "eagle-import") (part "resistor_R-US_R0603"))
    )
    (comp (ref "R87")
      (value "300")
      (footprint "eagle-import:R0603")
      (libsource (lib "eagle-import") (part "resistor_R-US_R0603"))
    )
    (comp (ref "R88")
      (value "100k")
      (footprint "eagle-import:R0603")
      (libsource (lib "eagle-import") (part "resistor_R-US_R0603"))
    )
    (comp (ref "R89")
      (value "56k")
      (footprint "eagle-import:R0603")
      (libsource (lib "eagle-import") (part "resistor_R-US_R0603"))
    )
    (comp (ref "R90")
      (value "100")
      (footprint "eagle-import:R0603")
      (libsource (lib "eagle-import") (part "resistor_R-US_R0603"))
    )
    (comp (ref "R91")
      (value "50k")
      (footprint "eagle-import:R0805")
      (libsource (lib "eagle-import") (part "R-US_R0805"))
    )
    (comp (ref "R92")
      (value "100")
      (footprint "eagle-import:R0603")
      (libsource (lib "eagle-import") (part "resistor_R-US_R0603"))
    )
    (comp (ref "R93")
      (value "10k")
      (footprint "eagle-import:R0603")
      (libsource (lib "eagle-import") (part "R-US_R0603"))
    )
    (comp (ref "R94")
      (value "200")
      (footprint "eagle-import:R0603")
      (libsource (lib "eagle-import") (part "R-US_R0603"))
    )
    (comp (ref "R95")
      (value "82k")
      (footprint "eagle-import:R0603")
      (libsource (lib "eagle-import") (part "resistor_R-US_R0603"))
    )
    (comp (ref "R96")
      (value "82k")
      (footprint "eagle-import:R0603")
      (libsource (lib "eagle-import") (part "resistor_R-US_R0603"))
    )
    (comp (ref "R97")
      (value "300")
      (footprint "eagle-import:R0603")
      (libsource (lib "eagle-import") (part "resistor_R-US_R0603"))
    )
    (comp (ref "R98")
      (value "100k")
      (footprint "eagle-import:R0603")
      (libsource (lib "eagle-import") (part "resistor_R-US_R0603"))
    )
    (comp (ref "R99")
      (value "56k")
      (footprint "eagle-import:R0603")
      (libsource (lib "eagle-import") (part "resistor_R-US_R0603"))
    )
    (comp (ref "R100")
      (value "100")
      (footprint "eagle-import:R0603")
      (libsource (lib "eagle-import") (part "resistor_R-US_R0603"))
    )
    (comp (ref "R101")
      (value "50k")
      (footprint "eagle-import:R0805")
      (libsource (lib "eagle-import") (part "R-US_R0805"))
    )
    (comp (ref "R102")
      (value "100")
      (footprint "eagle-import:R0603")
      (libsource (lib "eagle-import") (part "resistor_R-US_R0603"))
    )
    (comp (ref "R103")
      (value "10k")
      (footprint "eagle-import:R0603")
      (libsource (lib "eagle-import") (part "R-US_R0603"))
    )
    (comp (ref "R104")
      (value "200")
      (footprint "eagle-import:R0603")
      (libsource (lib "eagle-import") (part "R-US_R0603"))
    )
    (comp (ref "R105")
      (value "82k")
      (footprint "eagle-import:R0603")
      (libsource (lib "eagle-import") (part "resistor_R-US_R0603"))
    )
    (comp (ref "R106")
      (value "82k")
      (footprint "eagle-import:R0603")
      (libsource (lib "eagle-import") (part "resistor_R-US_R0603"))
    )
    (comp (ref "R107")
      (value "300")
      (footprint "eagle-import:R0603")
      (libsource (lib "eagle-import") (part "resistor_R-US_R0603"))
    )
    (comp (ref "R108")
      (value "100k")
      (footprint "eagle-import:R0603")
      (libsource (lib "eagle-import") (part "resistor_R-US_R0603"))
    )
    (comp (ref "R109")
      (value "56k")
      (footprint "eagle-import:R0603")
      (libsource (lib "eagle-import") (part "resistor_R-US_R0603"))
    )
    (comp (ref "R110")
      (value "100")
      (footprint "eagle-import:R0603")
      (libsource (lib "eagle-import") (part "resistor_R-US_R0603"))
    )
    (comp (ref "R111")
      (value "50k")
      (footprint "eagle-import:R0805")
      (libsource (lib "eagle-import") (part "R-US_R0805"))
    )
    (comp (ref "R112")
      (value "100")
      (footprint "eagle-import:R0603")
      (libsource (lib "eagle-import") (part "resistor_R-US_R0603"))
    )
    (comp (ref "R113")
      (value "10k")
      (footprint "eagle-import:R0603")
      (libsource (lib "eagle-import") (part "R-US_R0603"))
    )
    (comp (ref "R114")
      (value "200")
      (footprint "eagle-import:R0603")
      (libsource (lib "eagle-import") (part "R-US_R0603"))
    )
    (comp (ref "R115")
      (value "82k")
      (footprint "eagle-import:R0603")
      (libsource (lib "eagle-import") (part "resistor_R-US_R0603"))
    )
    (comp (ref "R116")
      (value "82k")
      (footprint "eagle-import:R0603")
      (libsource (lib "eagle-import") (part "resistor_R-US_R0603"))
    )
    (comp (ref "R117")
      (value "300")
      (footprint "eagle-import:R0603")
      (libsource (lib "eagle-import") (part "resistor_R-US_R0603"))
    )
    (comp (ref "R118")
      (value "100k")
      (footprint "eagle-import:R0603")
      (libsource (lib "eagle-import") (part "resistor_R-US_R0603"))
    )
    (comp (ref "R119")
      (value "56k")
      (footprint "eagle-import:R0603")
      (libsource (lib "eagle-import") (part "resistor_R-US_R0603"))
    )
    (comp (ref "R120")
      (value "100")
      (footprint "eagle-import:R0603")
      (libsource (lib "eagle-import") (part "resistor_R-US_R0603"))
    )
    (comp (ref "R121")
      (value "50k")
      (footprint "eagle-import:R0805")
      (libsource (lib "eagle-import") (part "R-US_R0805"))
    )
    (comp (ref "R122")
      (value "100")
      (footprint "eagle-import:R0603")
      (libsource (lib "eagle-import") (part "resistor_R-US_R0603"))
    )
    (comp (ref "R123")
      (value "10k")
      (footprint "eagle-import:R0603")
      (libsource (lib "eagle-import") (part "R-US_R0603"))
    )
    (comp (ref "R124")
      (value "200")
      (footprint "eagle-import:R0603")
      (libsource (lib "eagle-import") (part "R-US_R0603"))
    )
    (comp (ref "R125")
      (value "82k")
      (footprint "eagle-import:R0603")
      (libsource (lib "eagle-import") (part "resistor_R-US_R0603"))
    )
    (comp (ref "R126")
      (value "82k")
      (footprint "eagle-import:R0603")
      (libsource (lib "eagle-import") (part "resistor_R-US_R0603"))
    )
    (comp (ref "R127")
      (value "300")
      (footprint "eagle-import:R0603")
      (libsource (lib "eagle-import") (part "resistor_R-US_R0603"))
    )
    (comp (ref "R128")
      (value "100k")
      (footprint "eagle-import:R0603")
      (libsource (lib "eagle-import") (part "resistor_R-US_R0603"))
    )
    (comp (ref "R129")
      (value "56k")
      (footprint "eagle-import:R0603")
      (libsource (lib "eagle-import") (part "resistor_R-US_R0603"))
    )
    (comp (ref "R130")
      (value "100")
      (footprint "eagle-import:R0603")
      (libsource (lib "eagle-import") (part "resistor_R-US_R0603"))
    )
    (comp (ref "R131")
      (value "50k")
      (footprint "eagle-import:R0805")
      (libsource (lib "eagle-import") (part "R-US_R0805"))
    )
    (comp (ref "R132")
      (value "100")
      (footprint "eagle-import:R0603")
      (libsource (lib "eagle-import") (part "resistor_R-US_R0603"))
    )
    (comp (ref "R133")
      (value "10k")
      (footprint "eagle-import:R0603")
      (libsource (lib "eagle-import") (part "R-US_R0603"))
    )
    (comp (ref "R134")
      (value "200")
      (footprint "eagle-import:R0603")
      (libsource (lib "eagle-import") (part "R-US_R0603"))
    )
    (comp (ref "R135")
      (value "82k")
      (footprint "eagle-import:R0603")
      (libsource (lib "eagle-import") (part "resistor_R-US_R0603"))
    )
    (comp (ref "R136")
      (value "82k")
      (footprint "eagle-import:R0603")
      (libsource (lib "eagle-import") (part "resistor_R-US_R0603"))
    )
    (comp (ref "R137")
      (value "300")
      (footprint "eagle-import:R0603")
      (libsource (lib "eagle-import") (part "resistor_R-US_R0603"))
    )
    (comp (ref "R138")
      (value "100k")
      (footprint "eagle-import:R0603")
      (libsource (lib "eagle-import") (part "resistor_R-US_R0603"))
    )
    (comp (ref "R139")
      (value "56k")
      (footprint "eagle-import:R0603")
      (libsource (lib "eagle-import") (part "resistor_R-US_R0603"))
    )
    (comp (ref "R140")
      (value "100")
      (footprint "eagle-import:R0603")
      (libsource (lib "eagle-import") (part "resistor_R-US_R0603"))
    )
    (comp (ref "U$1")
      (value "INA101KU")
      (footprint "eagle-import:SOIC167.5MM")
      (libsource (lib "eagle-import") (part "INA101KUINA101KU"))
    )
    (comp (ref "U$2")
      (value "LMC6492")
      (footprint "eagle-import:SOIC14")
      (libsource (lib "eagle-import") (part "LMC6492"))
    )
    (comp (ref "U$3")
      (value "PV36504")
      (footprint "eagle-import:PV36W")
      (libsource (lib "eagle-import") (part "PV36"))
    )
    (comp (ref "U$4")
      (value "INA101KU")
      (footprint "eagle-import:SOIC167.5MM")
      (libsource (lib "eagle-import") (part "INA101KUINA101KU"))
    )
    (comp (ref "U$5")
      (value "LMC6492")
      (footprint "eagle-import:SOIC14")
      (libsource (lib "eagle-import") (part "LMC6492"))
    )
    (comp (ref "U$6")
      (value "PV36504")
      (footprint "eagle-import:PV36W")
      (libsource (lib "eagle-import") (part "PV36"))
    )
    (comp (ref "U$7")
      (value "2PIN")
      (footprint "eagle-import:2PIN")
      (libsource (lib "eagle-import") (part "2PIN"))
    )
    (comp (ref "U$8")
      (value "INA101KU")
      (footprint "eagle-import:SOIC167.5MM")
      (libsource (lib "eagle-import") (part "INA101KUINA101KU"))
    )
    (comp (ref "U$9")
      (value "LMC6492")
      (footprint "eagle-import:SOIC14")
      (libsource (lib "eagle-import") (part "LMC6492"))
    )
    (comp (ref "U$10")
      (value "2PIN")
      (footprint "eagle-import:2PIN")
      (libsource (lib "eagle-import") (part "2PIN"))
    )
    (comp (ref "U$11")
      (value "PV36504")
      (footprint "eagle-import:PV36W")
      (libsource (lib "eagle-import") (part "PV36"))
    )
    (comp (ref "U$12")
      (value "2PIN")
      (footprint "eagle-import:2PIN")
      (libsource (lib "eagle-import") (part "2PIN"))
    )
    (comp (ref "U$13")
      (value "INA101KU")
      (footprint "eagle-import:SOIC167.5MM")
      (libsource (lib "eagle-import") (part "INA101KUINA101KU"))
    )
    (comp (ref "U$14")
      (value "LMC6492")
      (footprint "eagle-import:SOIC14")
      (libsource (lib "eagle-import") (part "LMC6492"))
    )
    (comp (ref "U$15")
      (value "PV36504")
      (footprint "eagle-import:PV36W")
      (libsource (lib "eagle-import") (part "PV36"))
    )
    (comp (ref "U$16")
      (value "2PIN")
      (footprint "eagle-import:2PIN")
      (libsource (lib "eagle-import") (part "2PIN"))
    )
    (comp (ref "U$17")
      (value "INA101KU")
      (footprint "eagle-import:SOIC167.5MM")
      (libsource (lib "eagle-import") (part "INA101KUINA101KU"))
    )
    (comp (ref "U$18")
      (value "LMC6492")
      (footprint "eagle-import:SOIC14")
      (libsource (lib "eagle-import") (part "LMC6492"))
    )
    (comp (ref "U$19")
      (value "PV36504")
      (footprint "eagle-import:PV36W")
      (libsource (lib "eagle-import") (part "PV36"))
    )
    (comp (ref "U$20")
      (value "2PIN")
      (footprint "eagle-import:2PIN")
      (libsource (lib "eagle-import") (part "2PIN"))
    )
    (comp (ref "U$21")
      (value "INA101KU")
      (footprint "eagle-import:SOIC167.5MM")
      (libsource (lib "eagle-import") (part "INA101KUINA101KU"))
    )
    (comp (ref "U$22")
      (value "LMC6492")
      (footprint "eagle-import:SOIC14")
      (libsource (lib "eagle-import") (part "LMC6492"))
    )
    (comp (ref "U$23")
      (value "PV36504")
      (footprint "eagle-import:PV36W")
      (libsource (lib "eagle-import") (part "PV36"))
    )
    (comp (ref "U$24")
      (value "2PIN")
      (footprint "eagle-import:2PIN")
      (libsource (lib "eagle-import") (part "2PIN"))
    )
    (comp (ref "U$25")
      (value "INA101KU")
      (footprint "eagle-import:SOIC167.5MM")
      (libsource (lib "eagle-import") (part "INA101KUINA101KU"))
    )
    (comp (ref "U$26")
      (value "LMC6492")
      (footprint "eagle-import:SOIC14")
      (libsource (lib "eagle-import") (part "LMC6492"))
    )
    (comp (ref "U$27")
      (value "PV36504")
      (footprint "eagle-import:PV36W")
      (libsource (lib "eagle-import") (part "PV36"))
    )
    (comp (ref "U$28")
      (value "2PIN")
      (footprint "eagle-import:2PIN")
      (libsource (lib "eagle-import") (part "2PIN"))
    )
    (comp (ref "U$29")
      (value "INA101KU")
      (footprint "eagle-import:SOIC167.5MM")
      (libsource (lib "eagle-import") (part "INA101KUINA101KU"))
    )
    (comp (ref "U$30")
      (value "LMC6492")
      (footprint "eagle-import:SOIC14")
      (libsource (lib "eagle-import") (part "LMC6492"))
    )
    (comp (ref "U$31")
      (value "PV36504")
      (footprint "eagle-import:PV36W")
      (libsource (lib "eagle-import") (part "PV36"))
    )
    (comp (ref "U$32")
      (value "2PIN")
      (footprint "eagle-import:2PIN")
      (libsource (lib "eagle-import") (part "2PIN"))
    )
    (comp (ref "U$33")
      (value "INA101KU")
      (footprint "eagle-import:SOIC167.5MM")
      (libsource (lib "eagle-import") (part "INA101KUINA101KU"))
    )
    (comp (ref "U$34")
      (value "LMC6492")
      (footprint "eagle-import:SOIC14")
      (libsource (lib "eagle-import") (part "LMC6492"))
    )
    (comp (ref "U$35")
      (value "PV36504")
      (footprint "eagle-import:PV36W")
      (libsource (lib "eagle-import") (part "PV36"))
    )
    (comp (ref "U$36")
      (value "2PIN")
      (footprint "eagle-import:2PIN")
      (libsource (lib "eagle-import") (part "2PIN"))
    )
    (comp (ref "U$37")
      (value "INA101KU")
      (footprint "eagle-import:SOIC167.5MM")
      (libsource (lib "eagle-import") (part "INA101KUINA101KU"))
    )
    (comp (ref "U$38")
      (value "LMC6492")
      (footprint "eagle-import:SOIC14")
      (libsource (lib "eagle-import") (part "LMC6492"))
    )
    (comp (ref "U$39")
      (value "PV36504")
      (footprint "eagle-import:PV36W")
      (libsource (lib "eagle-import") (part "PV36"))
    )
    (comp (ref "U$40")
      (value "2PIN")
      (footprint "eagle-import:2PIN")
      (libsource (lib "eagle-import") (part "2PIN"))
    )
    (comp (ref "U$41")
      (value "INA101KU")
      (footprint "eagle-import:SOIC167.5MM")
      (libsource (lib "eagle-import") (part "INA101KUINA101KU"))
    )
    (comp (ref "U$42")
      (value "LMC6492")
      (footprint "eagle-import:SOIC14")
      (libsource (lib "eagle-import") (part "LMC6492"))
    )
    (comp (ref "U$43")
      (value "PV36504")
      (footprint "eagle-import:PV36W")
      (libsource (lib "eagle-import") (part "PV36"))
    )
    (comp (ref "U$44")
      (value "2PIN")
      (footprint "eagle-import:2PIN")
      (libsource (lib "eagle-import") (part "2PIN"))
    )
    (comp (ref "U$45")
      (value "INA101KU")
      (footprint "eagle-import:SOIC167.5MM")
      (libsource (lib "eagle-import") (part "INA101KUINA101KU"))
    )
    (comp (ref "U$46")
      (value "LMC6492")
      (footprint "eagle-import:SOIC14")
      (libsource (lib "eagle-import") (part "LMC6492"))
    )
    (comp (ref "U$47")
      (value "PV36504")
      (footprint "eagle-import:PV36W")
      (libsource (lib "eagle-import") (part "PV36"))
    )
    (comp (ref "U$48")
      (value "2PIN")
      (footprint "eagle-import:2PIN")
      (libsource (lib "eagle-import") (part "2PIN"))
    )
    (comp (ref "U$49")
      (value "INA101KU")
      (footprint "eagle-import:SOIC167.5MM")
      (libsource (lib "eagle-import") (part "INA101KUINA101KU"))
    )
    (comp (ref "U$50")
      (value "LMC6492")
      (footprint "eagle-import:SOIC14")
      (libsource (lib "eagle-import") (part "LMC6492"))
    )
    (comp (ref "U$51")
      (value "PV36504")
      (footprint "eagle-import:PV36W")
      (libsource (lib "eagle-import") (part "PV36"))
    )
    (comp (ref "U$52")
      (value "2PIN")
      (footprint "eagle-import:2PIN")
      (libsource (lib "eagle-import") (part "2PIN"))
    )
    (comp (ref "U$53")
      (value "INA101KU")
      (footprint "eagle-import:SOIC167.5MM")
      (libsource (lib "eagle-import") (part "INA101KUINA101KU"))
    )
    (comp (ref "U$54")
      (value "LMC6492")
      (footprint "eagle-import:SOIC14")
      (libsource (lib "eagle-import") (part "LMC6492"))
    )
    (comp (ref "U$55")
      (value "PV36504")
      (footprint "eagle-import:PV36W")
      (libsource (lib "eagle-import") (part "PV36"))
    )
    (comp (ref "U$56")
      (value "2PIN")
      (footprint "eagle-import:2PIN")
      (libsource (lib "eagle-import") (part "2PIN"))
    )
    (comp (ref "U$57")
      (value "3PIN")
      (footprint "eagle-import:3PIN")
      (libsource (lib "eagle-import") (part "3PIN"))
    )
    (comp (ref "U$58")
      (value "15PIN")
      (footprint "eagle-import:15PIN")
      (libsource (lib "eagle-import") (part "15PIN"))
    )
  )
  (nets
    (net (code "1") (name "/GND") (class "Default")
      (node (ref "C1") (pin "2") (pinfunction "2_2") (pintype "passive"))
      (node (ref "C11") (pin "2") (pinfunction "2_2") (pintype "passive"))
      (node (ref "C12") (pin "2") (pinfunction "2_2") (pintype "passive"))
      (node (ref "C13") (pin "2") (pinfunction "2_2") (pintype "passive"))
      (node (ref "C15") (pin "2") (pinfunction "2_2") (pintype "passive"))
      (node (ref "C16") (pin "2") (pinfunction "2_2") (pintype "passive"))
      (node (ref "C18") (pin "2") (pinfunction "2_2") (pintype "passive"))
      (node (ref "C19") (pin "2") (pinfunction "2_2") (pintype "passive"))
      (node (ref "C2") (pin "2") (pinfunction "2_2") (pintype "passive"))
      (node (ref "C20") (pin "2") (pinfunction "2_2") (pintype "passive"))
      (node (ref "C22") (pin "2") (pinfunction "2_2") (pintype "passive"))
      (node (ref "C23") (pin "2") (pinfunction "2_2") (pintype "passive"))
      (node (ref "C25") (pin "2") (pinfunction "2_2") (pintype "passive"))
      (node (ref "C26") (pin "2") (pinfunction "2_2") (pintype "passive"))
      (node (ref "C27") (pin "2") (pinfunction "2_2") (pintype "passive"))
      (node (ref "C29") (pin "2") (pinfunction "2_2") (pintype "passive"))
      (node (ref "C30") (pin "2") (pinfunction "2_2") (pintype "passive"))
      (node (ref "C32") (pin "2") (pinfunction "2_2") (pintype "passive"))
      (node (ref "C33") (pin "2") (pinfunction "2_2") (pintype "passive"))
      (node (ref "C34") (pin "2") (pinfunction "2_2") (pintype "passive"))
      (node (ref "C36") (pin "2") (pinfunction "2_2") (pintype "passive"))
      (node (ref "C37") (pin "2") (pinfunction "2_2") (pintype "passive"))
      (node (ref "C39") (pin "2") (pinfunction "2_2") (pintype "passive"))
      (node (ref "C4") (pin "2") (pinfunction "2_2") (pintype "passive"))
      (node (ref "C40") (pin "2") (pinfunction "2_2") (pintype "passive"))
      (node (ref "C41") (pin "2") (pinfunction "2_2") (pintype "passive"))
      (node (ref "C43") (pin "2") (pinfunction "2_2") (pintype "passive"))
      (node (ref "C44") (pin "2") (pinfunction "2_2") (pintype "passive"))
      (node (ref "C46") (pin "2") (pinfunction "2_2") (pintype "passive"))
      (node (ref "C47") (pin "2") (pinfunction "2_2") (pintype "passive"))
      (node (ref "C48") (pin "2") (pinfunction "2_2") (pintype "passive"))
      (node (ref "C5") (pin "2") (pinfunction "2_2") (pintype "passive"))
      (node (ref "C50") (pin "2") (pinfunction "2_2") (pintype "passive"))
      (node (ref "C51") (pin "2") (pinfunction "2_2") (pintype "passive"))
      (node (ref "C53") (pin "2") (pinfunction "2_2") (pintype "passive"))
      (node (ref "C54") (pin "2") (pinfunction "2_2") (pintype "passive"))
      (node (ref "C55") (pin "2") (pinfunction "2_2") (pintype "passive"))
      (node (ref "C57") (pin "2") (pinfunction "2_2") (pintype "passive"))
      (node (ref "C58") (pin "2") (pinfunction "2_2") (pintype "passive"))
      (node (ref "C6") (pin "2") (pinfunction "2_2") (pintype "passive"))
      (node (ref "C60") (pin "2") (pinfunction "2_2") (pintype "passive"))
      (node (ref "C61") (pin "2") (pinfunction "2_2") (pintype "passive"))
      (node (ref "C62") (pin "2") (pinfunction "2_2") (pintype "passive"))
      (node (ref "C64") (pin "2") (pinfunction "2_2") (pintype "passive"))
      (node (ref "C65") (pin "2") (pinfunction "2_2") (pintype "passive"))
      (node (ref "C67") (pin "2") (pinfunction "2_2") (pintype "passive"))
      (node (ref "C68") (pin "2") (pinfunction "2_2") (pintype "passive"))
      (node (ref "C69") (pin "2") (pinfunction "2_2") (pintype "passive"))
      (node (ref "C71") (pin "2") (pinfunction "2_2") (pintype "passive"))
      (node (ref "C72") (pin "2") (pinfunction "2_2") (pintype "passive"))
      (node (ref "C74") (pin "2") (pinfunction "2_2") (pintype "passive"))
      (node (ref "C75") (pin "2") (pinfunction "2_2") (pintype "passive"))
      (node (ref "C76") (pin "2") (pinfunction "2_2") (pintype "passive"))
      (node (ref "C78") (pin "2") (pinfunction "2_2") (pintype "passive"))
      (node (ref "C79") (pin "2") (pinfunction "2_2") (pintype "passive"))
      (node (ref "C8") (pin "2") (pinfunction "2_2") (pintype "passive"))
      (node (ref "C81") (pin "2") (pinfunction "2_2") (pintype "passive"))
      (node (ref "C82") (pin "2") (pinfunction "2_2") (pintype "passive"))
      (node (ref "C83") (pin "2") (pinfunction "2_2") (pintype "passive"))
      (node (ref "C85") (pin "2") (pinfunction "2_2") (pintype "passive"))
      (node (ref "C86") (pin "2") (pinfunction "2_2") (pintype "passive"))
      (node (ref "C88") (pin "2") (pinfunction "2_2") (pintype "passive"))
      (node (ref "C89") (pin "2") (pinfunction "2_2") (pintype "passive"))
      (node (ref "C9") (pin "2") (pinfunction "2_2") (pintype "passive"))
      (node (ref "C90") (pin "2") (pinfunction "2_2") (pintype "passive"))
      (node (ref "C92") (pin "2") (pinfunction "2_2") (pintype "passive"))
      (node (ref "C93") (pin "2") (pinfunction "2_2") (pintype "passive"))
      (node (ref "C95") (pin "2") (pinfunction "2_2") (pintype "passive"))
      (node (ref "C96") (pin "2") (pinfunction "2_2") (pintype "passive"))
      (node (ref "C97") (pin "2") (pinfunction "2_2") (pintype "passive"))
      (node (ref "GND") (pin "1") (pinfunction "1_1") (pintype "passive"))
      (node (ref "R103") (pin "1") (pinfunction "1_1") (pintype "passive"))
      (node (ref "R107") (pin "2") (pinfunction "2_2") (pintype "passive"))
      (node (ref "R108") (pin "2") (pinfunction "2_2") (pintype "passive"))
      (node (ref "R113") (pin "1") (pinfunction "1_1") (pintype "passive"))
      (node (ref "R117") (pin "2") (pinfunction "2_2") (pintype "passive"))
      (node (ref "R118") (pin "2") (pinfunction "2_2") (pintype "passive"))
      (node (ref "R123") (pin "1") (pinfunction "1_1") (pintype "passive"))
      (node (ref "R127") (pin "2") (pinfunction "2_2") (pintype "passive"))
      (node (ref "R128") (pin "2") (pinfunction "2_2") (pintype "passive"))
      (node (ref "R13") (pin "1") (pinfunction "1_1") (pintype "passive"))
      (node (ref "R133") (pin "1") (pinfunction "1_1") (pintype "passive"))
      (node (ref "R137") (pin "2") (pinfunction "2_2") (pintype "passive"))
      (node (ref "R138") (pin "2") (pinfunction "2_2") (pintype "passive"))
      (node (ref "R17") (pin "2") (pinfunction "2_2") (pintype "passive"))
      (node (ref "R18") (pin "2") (pinfunction "2_2") (pintype "passive"))
      (node (ref "R23") (pin "1") (pinfunction "1_1") (pintype "passive"))
      (node (ref "R27") (pin "2") (pinfunction "2_2") (pintype "passive"))
      (node (ref "R28") (pin "2") (pinfunction "2_2") (pintype "passive"))
      (node (ref "R3") (pin "1") (pinfunction "1_1") (pintype "passive"))
      (node (ref "R33") (pin "1") (pinfunction "1_1") (pintype "passive"))
      (node (ref "R37") (pin "2") (pinfunction "2_2") (pintype "passive"))
      (node (ref "R38") (pin "2") (pinfunction "2_2") (pintype "passive"))
      (node (ref "R43") (pin "1") (pinfunction "1_1") (pintype "passive"))
      (node (ref "R47") (pin "2") (pinfunction "2_2") (pintype "passive"))
      (node (ref "R48") (pin "2") (pinfunction "2_2") (pintype "passive"))
      (node (ref "R53") (pin "1") (pinfunction "1_1") (pintype "passive"))
      (node (ref "R57") (pin "2") (pinfunction "2_2") (pintype "passive"))
      (node (ref "R58") (pin "2") (pinfunction "2_2") (pintype "passive"))
      (node (ref "R63") (pin "1") (pinfunction "1_1") (pintype "passive"))
      (node (ref "R67") (pin "2") (pinfunction "2_2") (pintype "passive"))
      (node (ref "R68") (pin "2") (pinfunction "2_2") (pintype "passive"))
      (node (ref "R7") (pin "2") (pinfunction "2_2") (pintype "passive"))
      (node (ref "R73") (pin "1") (pinfunction "1_1") (pintype "passive"))
      (node (ref "R77") (pin "2") (pinfunction "2_2") (pintype "passive"))
      (node (ref "R78") (pin "2") (pinfunction "2_2") (pintype "passive"))
      (node (ref "R8") (pin "2") (pinfunction "2_2") (pintype "passive"))
      (node (ref "R83") (pin "1") (pinfunction "1_1") (pintype "passive"))
      (node (ref "R87") (pin "2") (pinfunction "2_2") (pintype "passive"))
      (node (ref "R88") (pin "2") (pinfunction "2_2") (pintype "passive"))
      (node (ref "R93") (pin "1") (pinfunction "1_1") (pintype "passive"))
      (node (ref "R97") (pin "2") (pinfunction "2_2") (pintype "passive"))
      (node (ref "R98") (pin "2") (pinfunction "2_2") (pintype "passive"))
      (node (ref "U$14") (pin "10") (pinfunction "INC+_10") (pintype "bidirectional"))
      (node (ref "U$14") (pin "3") (pinfunction "INA+_3") (pintype "bidirectional"))
      (node (ref "U$18") (pin "10") (pinfunction "INC+_10") (pintype "bidirectional"))
      (node (ref "U$18") (pin "3") (pinfunction "INA+_3") (pintype "bidirectional"))
      (node (ref "U$2") (pin "10") (pinfunction "INC+_10") (pintype "bidirectional"))
      (node (ref "U$2") (pin "3") (pinfunction "INA+_3") (pintype "bidirectional"))
      (node (ref "U$22") (pin "10") (pinfunction "INC+_10") (pintype "bidirectional"))
      (node (ref "U$22") (pin "3") (pinfunction "INA+_3") (pintype "bidirectional"))
      (node (ref "U$26") (pin "10") (pinfunction "INC+_10") (pintype "bidirectional"))
      (node (ref "U$26") (pin "3") (pinfunction "INA+_3") (pintype "bidirectional"))
      (node (ref "U$30") (pin "10") (pinfunction "INC+_10") (pintype "bidirectional"))
      (node (ref "U$30") (pin "3") (pinfunction "INA+_3") (pintype "bidirectional"))
      (node (ref "U$34") (pin "10") (pinfunction "INC+_10") (pintype "bidirectional"))
      (node (ref "U$34") (pin "3") (pinfunction "INA+_3") (pintype "bidirectional"))
      (node (ref "U$38") (pin "10") (pinfunction "INC+_10") (pintype "bidirectional"))
      (node (ref "U$38") (pin "3") (pinfunction "INA+_3") (pintype "bidirectional"))
      (node (ref "U$42") (pin "10") (pinfunction "INC+_10") (pintype "bidirectional"))
      (node (ref "U$42") (pin "3") (pinfunction "INA+_3") (pintype "bidirectional"))
      (node (ref "U$46") (pin "10") (pinfunction "INC+_10") (pintype "bidirectional"))
      (node (ref "U$46") (pin "3") (pinfunction "INA+_3") (pintype "bidirectional"))
      (node (ref "U$5") (pin "10") (pinfunction "INC+_10") (pintype "bidirectional"))
      (node (ref "U$5") (pin "3") (pinfunction "INA+_3") (pintype "bidirectional"))
      (node (ref "U$50") (pin "10") (pinfunction "INC+_10") (pintype "bidirectional"))
      (node (ref "U$50") (pin "3") (pinfunction "INA+_3") (pintype "bidirectional"))
      (node (ref "U$54") (pin "10") (pinfunction "INC+_10") (pintype "bidirectional"))
      (node (ref "U$54") (pin "3") (pinfunction "INA+_3") (pintype "bidirectional"))
      (node (ref "U$57") (pin "1") (pinfunction "1_1") (pintype "bidirectional"))
      (node (ref "U$58") (pin "15") (pinfunction "15_15") (pintype "bidirectional"))
      (node (ref "U$9") (pin "10") (pinfunction "INC+_10") (pintype "bidirectional"))
      (node (ref "U$9") (pin "3") (pinfunction "INA+_3") (pintype "bidirectional"))
    )
    (net (code "2") (name "/VCC+") (class "Default")
      (node (ref "C1") (pin "1") (pinfunction "1_1") (pintype "passive"))
      (node (ref "C11") (pin "1") (pinfunction "1_1") (pintype "passive"))
      (node (ref "C15") (pin "1") (pinfunction "1_1") (pintype "passive"))
      (node (ref "C18") (pin "1") (pinfunction "1_1") (pintype "passive"))
      (node (ref "C22") (pin "1") (pinfunction "1_1") (pintype "passive"))
      (node (ref "C25") (pin "1") (pinfunction "1_1") (pintype "passive"))
      (node (ref "C29") (pin "1") (pinfunction "1_1") (pintype "passive"))
      (node (ref "C32") (pin "1") (pinfunction "1_1") (pintype "passive"))
      (node (ref "C36") (pin "1") (pinfunction "1_1") (pintype "passive"))
      (node (ref "C39") (pin "1") (pinfunction "1_1") (pintype "passive"))
      (node (ref "C4") (pin "1") (pinfunction "1_1") (pintype "passive"))
      (node (ref "C43") (pin "1") (pinfunction "1_1") (pintype "passive"))
      (node (ref "C46") (pin "1") (pinfunction "1_1") (pintype "passive"))
      (node (ref "C50") (pin "1") (pinfunction "1_1") (pintype "passive"))
      (node (ref "C53") (pin "1") (pinfunction "1_1") (pintype "passive"))
      (node (ref "C57") (pin "1") (pinfunction "1_1") (pintype "passive"))
      (node (ref "C60") (pin "1") (pinfunction "1_1") (pintype "passive"))
      (node (ref "C64") (pin "1") (pinfunction "1_1") (pintype "passive"))
      (node (ref "C67") (pin "1") (pinfunction "1_1") (pintype "passive"))
      (node (ref "C71") (pin "1") (pinfunction "1_1") (pintype "passive"))
      (node (ref "C74") (pin "1") (pinfunction "1_1") (pintype "passive"))
      (node (ref "C78") (pin "1") (pinfunction "1_1") (pintype "passive"))
      (node (ref "C8") (pin "1") (pinfunction "1_1") (pintype "passive"))
      (node (ref "C81") (pin "1") (pinfunction "1_1") (pintype "passive"))
      (node (ref "C85") (pin "1") (pinfunction "1_1") (pintype "passive"))
      (node (ref "C88") (pin "1") (pinfunction "1_1") (pintype "passive"))
      (node (ref "C92") (pin "1") (pinfunction "1_1") (pintype "passive"))
      (node (ref "C95") (pin "1") (pinfunction "1_1") (pintype "passive"))
      (node (ref "U$1") (pin "2") (pinfunction "VCC+_2") (pintype "bidirectional"))
      (node (ref "U$13") (pin "2") (pinfunction "VCC+_2") (pintype "bidirectional"))
      (node (ref "U$14") (pin "4") (pinfunction "VCC+_4") (pintype "bidirectional"))
      (node (ref "U$17") (pin "2") (pinfunction "VCC+_2") (pintype "bidirectional"))
      (node (ref "U$18") (pin "4") (pinfunction "VCC+_4") (pintype "bidirectional"))
      (node (ref "U$2") (pin "4") (pinfunction "VCC+_4") (pintype "bidirectional"))
      (node (ref "U$21") (pin "2") (pinfunction "VCC+_2") (pintype "bidirectional"))
      (node (ref "U$22") (pin "4") (pinfunction "VCC+_4") (pintype "bidirectional"))
      (node (ref "U$25") (pin "2") (pinfunction "VCC+_2") (pintype "bidirectional"))
      (node (ref "U$26") (pin "4") (pinfunction "VCC+_4") (pintype "bidirectional"))
      (node (ref "U$29") (pin "2") (pinfunction "VCC+_2") (pintype "bidirectional"))
      (node (ref "U$30") (pin "4") (pinfunction "VCC+_4") (pintype "bidirectional"))
      (node (ref "U$33") (pin "2") (pinfunction "VCC+_2") (pintype "bidirectional"))
      (node (ref "U$34") (pin "4") (pinfunction "VCC+_4") (pintype "bidirectional"))
      (node (ref "U$37") (pin "2") (pinfunction "VCC+_2") (pintype "bidirectional"))
      (node (ref "U$38") (pin "4") (pinfunction "VCC+_4") (pintype "bidirectional"))
      (node (ref "U$4") (pin "2") (pinfunction "VCC+_2") (pintype "bidirectional"))
      (node (ref "U$41") (pin "2") (pinfunction "VCC+_2") (pintype "bidirectional"))
      (node (ref "U$42") (pin "4") (pinfunction "VCC+_4") (pintype "bidirectional"))
      (node (ref "U$45") (pin "2") (pinfunction "VCC+_2") (pintype "bidirectional"))
      (node (ref "U$46") (pin "4") (pinfunction "VCC+_4") (pintype "bidirectional"))
      (node (ref "U$49") (pin "2") (pinfunction "VCC+_2") (pintype "bidirectional"))
      (node (ref "U$5") (pin "4") (pinfunction "VCC+_4") (pintype "bidirectional"))
      (node (ref "U$50") (pin "4") (pinfunction "VCC+_4") (pintype "bidirectional"))
      (node (ref "U$53") (pin "2") (pinfunction "VCC+_2") (pintype "bidirectional"))
      (node (ref "U$54") (pin "4") (pinfunction "VCC+_4") (pintype "bidirectional"))
      (node (ref "U$57") (pin "3") (pinfunction "3_3") (pintype "bidirectional"))
      (node (ref "U$8") (pin "2") (pinfunction "VCC+_2") (pintype "bidirectional"))
      (node (ref "U$9") (pin "4") (pinfunction "VCC+_4") (pintype "bidirectional"))
    )
    (net (code "3") (name "/VCC-") (class "Default")
      (node (ref "C12") (pin "1") (pinfunction "1_1") (pintype "passive"))
      (node (ref "C16") (pin "1") (pinfunction "1_1") (pintype "passive"))
      (node (ref "C19") (pin "1") (pinfunction "1_1") (pintype "passive"))
      (node (ref "C2") (pin "1") (pinfunction "1_1") (pintype "passive"))
      (node (ref "C23") (pin "1") (pinfunction "1_1") (pintype "passive"))
      (node (ref "C26") (pin "1") (pinfunction "1_1") (pintype "passive"))
      (node (ref "C30") (pin "1") (pinfunction "1_1") (pintype "passive"))
      (node (ref "C33") (pin "1") (pinfunction "1_1") (pintype "passive"))
      (node (ref "C37") (pin "1") (pinfunction "1_1") (pintype "passive"))
      (node (ref "C40") (pin "1") (pinfunction "1_1") (pintype "passive"))
      (node (ref "C44") (pin "1") (pinfunction "1_1") (pintype "passive"))
      (node (ref "C47") (pin "1") (pinfunction "1_1") (pintype "passive"))
      (node (ref "C5") (pin "1") (pinfunction "1_1") (pintype "passive"))
      (node (ref "C51") (pin "1") (pinfunction "1_1") (pintype "passive"))
      (node (ref "C54") (pin "1") (pinfunction "1_1") (pintype "passive"))
      (node (ref "C58") (pin "1") (pinfunction "1_1") (pintype "passive"))
      (node (ref "C61") (pin "1") (pinfunction "1_1") (pintype "passive"))
      (node (ref "C65") (pin "1") (pinfunction "1_1") (pintype "passive"))
      (node (ref "C68") (pin "1") (pinfunction "1_1") (pintype "passive"))
      (node (ref "C72") (pin "1") (pinfunction "1_1") (pintype "passive"))
      (node (ref "C75") (pin "1") (pinfunction "1_1") (pintype "passive"))
      (node (ref "C79") (pin "1") (pinfunction "1_1") (pintype "passive"))
      (node (ref "C82") (pin "1") (pinfunction "1_1") (pintype "passive"))
      (node (ref "C86") (pin "1") (pinfunction "1_1") (pintype "passive"))
      (node (ref "C89") (pin "1") (pinfunction "1_1") (pintype "passive"))
      (node (ref "C9") (pin "1") (pinfunction "1_1") (pintype "passive"))
      (node (ref "C93") (pin "1") (pinfunction "1_1") (pintype "passive"))
      (node (ref "C96") (pin "1") (pinfunction "1_1") (pintype "passive"))
      (node (ref "U$1") (pin "15") (pinfunction "VCC-_15") (pintype "bidirectional"))
      (node (ref "U$13") (pin "15") (pinfunction "VCC-_15") (pintype "bidirectional"))
      (node (ref "U$14") (pin "11") (pinfunction "VCC-_11") (pintype "bidirectional"))
      (node (ref "U$17") (pin "15") (pinfunction "VCC-_15") (pintype "bidirectional"))
      (node (ref "U$18") (pin "11") (pinfunction "VCC-_11") (pintype "bidirectional"))
      (node (ref "U$2") (pin "11") (pinfunction "VCC-_11") (pintype "bidirectional"))
      (node (ref "U$21") (pin "15") (pinfunction "VCC-_15") (pintype "bidirectional"))
      (node (ref "U$22") (pin "11") (pinfunction "VCC-_11") (pintype "bidirectional"))
      (node (ref "U$25") (pin "15") (pinfunction "VCC-_15") (pintype "bidirectional"))
      (node (ref "U$26") (pin "11") (pinfunction "VCC-_11") (pintype "bidirectional"))
      (node (ref "U$29") (pin "15") (pinfunction "VCC-_15") (pintype "bidirectional"))
      (node (ref "U$30") (pin "11") (pinfunction "VCC-_11") (pintype "bidirectional"))
      (node (ref "U$33") (pin "15") (pinfunction "VCC-_15") (pintype "bidirectional"))
      (node (ref "U$34") (pin "11") (pinfunction "VCC-_11") (pintype "bidirectional"))
      (node (ref "U$37") (pin "15") (pinfunction "VCC-_15") (pintype "bidirectional"))
      (node (ref "U$38") (pin "11") (pinfunction "VCC-_11") (pintype "bidirectional"))
      (node (ref "U$4") (pin "15") (pinfunction "VCC-_15") (pintype "bidirectional"))
      (node (ref "U$41") (pin "15") (pinfunction "VCC-_15") (pintype "bidirectional"))
      (node (ref "U$42") (pin "11") (pinfunction "VCC-_11") (pintype "bidirectional"))
      (node (ref "U$45") (pin "15") (pinfunction "VCC-_15") (pintype "bidirectional"))
      (node (ref "U$46") (pin "11") (pinfunction "VCC-_11") (pintype "bidirectional"))
      (node (ref "U$49") (pin "15") (pinfunction "VCC-_15") (pintype "bidirectional"))
      (node (ref "U$5") (pin "11") (pinfunction "VCC-_11") (pintype "bidirectional"))
      (node (ref "U$50") (pin "11") (pinfunction "VCC-_11") (pintype "bidirectional"))
      (node (ref "U$53") (pin "15") (pinfunction "VCC-_15") (pintype "bidirectional"))
      (node (ref "U$54") (pin "11") (pinfunction "VCC-_11") (pintype "bidirectional"))
      (node (ref "U$57") (pin "2") (pinfunction "2_2") (pintype "bidirectional"))
      (node (ref "U$8") (pin "15") (pinfunction "VCC-_15") (pintype "bidirectional"))
      (node (ref "U$9") (pin "11") (pinfunction "VCC-_11") (pintype "bidirectional"))
    )
    (net (code "4") (name "Net-(C7-Pad1)") (class "Default")
      (node (ref "C7") (pin "1") (pinfunction "1_1") (pintype "passive"))
      (node (ref "R5") (pin "2") (pinfunction "2_2") (pintype "passive"))
      (node (ref "R6") (pin "2") (pinfunction "2_2") (pintype "passive"))
    )
    (net (code "5") (name "Net-(C14-Pad1)") (class "Default")
      (node (ref "C14") (pin "1") (pinfunction "1_1") (pintype "passive"))
      (node (ref "R15") (pin "2") (pinfunction "2_2") (pintype "passive"))
      (node (ref "R16") (pin "2") (pinfunction "2_2") (pintype "passive"))
    )
    (net (code "6") (name "Net-(C21-Pad1)") (class "Default")
      (node (ref "C21") (pin "1") (pinfunction "1_1") (pintype "passive"))
      (node (ref "R25") (pin "2") (pinfunction "2_2") (pintype "passive"))
      (node (ref "R26") (pin "2") (pinfunction "2_2") (pintype "passive"))
    )
    (net (code "7") (name "Net-(C28-Pad1)") (class "Default")
      (node (ref "C28") (pin "1") (pinfunction "1_1") (pintype "passive"))
      (node (ref "R35") (pin "2") (pinfunction "2_2") (pintype "passive"))
      (node (ref "R36") (pin "2") (pinfunction "2_2") (pintype "passive"))
    )
    (net (code "8") (name "Net-(C35-Pad1)") (class "Default")
      (node (ref "C35") (pin "1") (pinfunction "1_1") (pintype "passive"))
      (node (ref "R45") (pin "2") (pinfunction "2_2") (pintype "passive"))
      (node (ref "R46") (pin "2") (pinfunction "2_2") (pintype "passive"))
    )
    (net (code "9") (name "Net-(C42-Pad1)") (class "Default")
      (node (ref "C42") (pin "1") (pinfunction "1_1") (pintype "passive"))
      (node (ref "R55") (pin "2") (pinfunction "2_2") (pintype "passive"))
      (node (ref "R56") (pin "2") (pinfunction "2_2") (pintype "passive"))
    )
    (net (code "10") (name "Net-(C49-Pad1)") (class "Default")
      (node (ref "C49") (pin "1") (pinfunction "1_1") (pintype "passive"))
      (node (ref "R65") (pin "2") (pinfunction "2_2") (pintype "passive"))
      (node (ref "R66") (pin "2") (pinfunction "2_2") (pintype "passive"))
    )
    (net (code "11") (name "Net-(C56-Pad1)") (class "Default")
      (node (ref "C56") (pin "1") (pinfunction "1_1") (pintype "passive"))
      (node (ref "R75") (pin "2") (pinfunction "2_2") (pintype "passive"))
      (node (ref "R76") (pin "2") (pinfunction "2_2") (pintype "passive"))
    )
    (net (code "12") (name "Net-(C63-Pad1)") (class "Default")
      (node (ref "C63") (pin "1") (pinfunction "1_1") (pintype "passive"))
      (node (ref "R85") (pin "2") (pinfunction "2_2") (pintype "passive"))
      (node (ref "R86") (pin "2") (pinfunction "2_2") (pintype "passive"))
    )
    (net (code "13") (name "Net-(C70-Pad1)") (class "Default")
      (node (ref "C70") (pin "1") (pinfunction "1_1") (pintype "passive"))
      (node (ref "R95") (pin "2") (pinfunction "2_2") (pintype "passive"))
      (node (ref "R96") (pin "2") (pinfunction "2_2") (pintype "passive"))
    )
    (net (code "14") (name "Net-(C77-Pad1)") (class "Default")
      (node (ref "C77") (pin "1") (pinfunction "1_1") (pintype "passive"))
      (node (ref "R105") (pin "2") (pinfunction "2_2") (pintype "passive"))
      (node (ref "R106") (pin "2") (pinfunction "2_2") (pintype "passive"))
    )
    (net (code "15") (name "Net-(C84-Pad1)") (class "Default")
      (node (ref "C84") (pin "1") (pinfunction "1_1") (pintype "passive"))
      (node (ref "R115") (pin "2") (pinfunction "2_2") (pintype "passive"))
      (node (ref "R116") (pin "2") (pinfunction "2_2") (pintype "passive"))
    )
    (net (code "16") (name "Net-(C91-Pad1)") (class "Default")
      (node (ref "C91") (pin "1") (pinfunction "1_1") (pintype "passive"))
      (node (ref "R125") (pin "2") (pinfunction "2_2") (pintype "passive"))
      (node (ref "R126") (pin "2") (pinfunction "2_2") (pintype "passive"))
    )
    (net (code "17") (name "Net-(C98-Pad1)") (class "Default")
      (node (ref "C98") (pin "1") (pinfunction "1_1") (pintype "passive"))
      (node (ref "R135") (pin "2") (pinfunction "2_2") (pintype "passive"))
      (node (ref "R136") (pin "2") (pinfunction "2_2") (pintype "passive"))
    )
    (net (code "18") (name "Net-(D1-A)") (class "Default")
      (node (ref "D1") (pin "1") (pinfunction "A_1") (pintype "passive"))
      (node (ref "U$2") (pin "8") (pinfunction "OUTC_8") (pintype "bidirectional"))
    )
    (net (code "19") (name "Net-(D1-C)") (class "Default")
      (node (ref "D1") (pin "3") (pinfunction "C_3") (pintype "passive"))
      (node (ref "R10") (pin "2") (pinfunction "2_2") (pintype "passive"))
      (node (ref "R5") (pin "1") (pinfunction "1_1") (pintype "passive"))
      (node (ref "R7") (pin "1") (pinfunction "1_1") (pintype "passive"))
    )
    (net (code "20") (name "Net-(D2-A)") (class "Default")
      (node (ref "D2") (pin "1") (pinfunction "A_1") (pintype "passive"))
      (node (ref "U$5") (pin "8") (pinfunction "OUTC_8") (pintype "bidirectional"))
    )
    (net (code "21") (name "Net-(D2-C)") (class "Default")
      (node (ref "D2") (pin "3") (pinfunction "C_3") (pintype "passive"))
      (node (ref "R15") (pin "1") (pinfunction "1_1") (pintype "passive"))
      (node (ref "R17") (pin "1") (pinfunction "1_1") (pintype "passive"))
      (node (ref "R20") (pin "2") (pinfunction "2_2") (pintype "passive"))
    )
    (net (code "22") (name "Net-(D3-A)") (class "Default")
      (node (ref "D3") (pin "1") (pinfunction "A_1") (pintype "passive"))
      (node (ref "U$9") (pin "8") (pinfunction "OUTC_8") (pintype "bidirectional"))
    )
    (net (code "23") (name "Net-(D3-C)") (class "Default")
      (node (ref "D3") (pin "3") (pinfunction "C_3") (pintype "passive"))
      (node (ref "R25") (pin "1") (pinfunction "1_1") (pintype "passive"))
      (node (ref "R27") (pin "1") (pinfunction "1_1") (pintype "passive"))
      (node (ref "R30") (pin "2") (pinfunction "2_2") (pintype "passive"))
    )
    (net (code "24") (name "Net-(D4-A)") (class "Default")
      (node (ref "D4") (pin "1") (pinfunction "A_1") (pintype "passive"))
      (node (ref "U$14") (pin "8") (pinfunction "OUTC_8") (pintype "bidirectional"))
    )
    (net (code "25") (name "Net-(D4-C)") (class "Default")
      (node (ref "D4") (pin "3") (pinfunction "C_3") (pintype "passive"))
      (node (ref "R35") (pin "1") (pinfunction "1_1") (pintype "passive"))
      (node (ref "R37") (pin "1") (pinfunction "1_1") (pintype "passive"))
      (node (ref "R40") (pin "2") (pinfunction "2_2") (pintype "passive"))
    )
    (net (code "26") (name "Net-(D5-A)") (class "Default")
      (node (ref "D5") (pin "1") (pinfunction "A_1") (pintype "passive"))
      (node (ref "U$18") (pin "8") (pinfunction "OUTC_8") (pintype "bidirectional"))
    )
    (net (code "27") (name "Net-(D5-C)") (class "Default")
      (node (ref "D5") (pin "3") (pinfunction "C_3") (pintype "passive"))
      (node (ref "R45") (pin "1") (pinfunction "1_1") (pintype "passive"))
      (node (ref "R47") (pin "1") (pinfunction "1_1") (pintype "passive"))
      (node (ref "R50") (pin "2") (pinfunction "2_2") (pintype "passive"))
    )
    (net (code "28") (name "Net-(D6-A)") (class "Default")
      (node (ref "D6") (pin "1") (pinfunction "A_1") (pintype "passive"))
      (node (ref "U$22") (pin "8") (pinfunction "OUTC_8") (pintype "bidirectional"))
    )
    (net (code "29") (name "Net-(D6-C)") (class "Default")
      (node (ref "D6") (pin "3") (pinfunction "C_3") (pintype "passive"))
      (node (ref "R55") (pin "1") (pinfunction "1_1") (pintype "passive"))
      (node (ref "R57") (pin "1") (pinfunction "1_1") (pintype "passive"))
      (node (ref "R60") (pin "2") (pinfunction "2_2") (pintype "passive"))
    )
    (net (code "30") (name "Net-(D7-A)") (class "Default")
      (node (ref "D7") (pin "1") (pinfunction "A_1") (pintype "passive"))
      (node (ref "U$26") (pin "8") (pinfunction "OUTC_8") (pintype "bidirectional"))
    )
    (net (code "31") (name "Net-(D7-C)") (class "Default")
      (node (ref "D7") (pin "3") (pinfunction "C_3") (pintype "passive"))
      (node (ref "R65") (pin "1") (pinfunction "1_1") (pintype "passive"))
      (node (ref "R67") (pin "1") (pinfunction "1_1") (pintype "passive"))
      (node (ref "R70") (pin "2") (pinfunction "2_2") (pintype "passive"))
    )
    (net (code "32") (name "Net-(D8-A)") (class "Default")
      (node (ref "D8") (pin "1") (pinfunction "A_1") (pintype "passive"))
      (node (ref "U$30") (pin "8") (pinfunction "OUTC_8") (pintype "bidirectional"))
    )
    (net (code "33") (name "Net-(D8-C)") (class "Default")
      (node (ref "D8") (pin "3") (pinfunction "C_3") (pintype "passive"))
      (node (ref "R75") (pin "1") (pinfunction "1_1") (pintype "passive"))
      (node (ref "R77") (pin "1") (pinfunction "1_1") (pintype "passive"))
      (node (ref "R80") (pin "2") (pinfunction "2_2") (pintype "passive"))
    )
    (net (code "34") (name "Net-(D9-A)") (class "Default")
      (node (ref "D9") (pin "1") (pinfunction "A_1") (pintype "passive"))
      (node (ref "U$34") (pin "8") (pinfunction "OUTC_8") (pintype "bidirectional"))
    )
    (net (code "35") (name "Net-(D9-C)") (class "Default")
      (node (ref "D9") (pin "3") (pinfunction "C_3") (pintype "passive"))
      (node (ref "R85") (pin "1") (pinfunction "1_1") (pintype "passive"))
      (node (ref "R87") (pin "1") (pinfunction "1_1") (pintype "passive"))
      (node (ref "R90") (pin "2") (pinfunction "2_2") (pintype "passive"))
    )
    (net (code "36") (name "Net-(D10-A)") (class "Default")
      (node (ref "D10") (pin "1") (pinfunction "A_1") (pintype "passive"))
      (node (ref "U$38") (pin "8") (pinfunction "OUTC_8") (pintype "bidirectional"))
    )
    (net (code "37") (name "Net-(D10-C)") (class "Default")
      (node (ref "D10") (pin "3") (pinfunction "C_3") (pintype "passive"))
      (node (ref "R100") (pin "2") (pinfunction "2_2") (pintype "passive"))
      (node (ref "R95") (pin "1") (pinfunction "1_1") (pintype "passive"))
      (node (ref "R97") (pin "1") (pinfunction "1_1") (pintype "passive"))
    )
    (net (code "38") (name "Net-(D11-A)") (class "Default")
      (node (ref "D11") (pin "1") (pinfunction "A_1") (pintype "passive"))
      (node (ref "U$42") (pin "8") (pinfunction "OUTC_8") (pintype "bidirectional"))
    )
    (net (code "39") (name "Net-(D11-C)") (class "Default")
      (node (ref "D11") (pin "3") (pinfunction "C_3") (pintype "passive"))
      (node (ref "R105") (pin "1") (pinfunction "1_1") (pintype "passive"))
      (node (ref "R107") (pin "1") (pinfunction "1_1") (pintype "passive"))
      (node (ref "R110") (pin "2") (pinfunction "2_2") (pintype "passive"))
    )
    (net (code "40") (name "Net-(D12-A)") (class "Default")
      (node (ref "D12") (pin "1") (pinfunction "A_1") (pintype "passive"))
      (node (ref "U$46") (pin "8") (pinfunction "OUTC_8") (pintype "bidirectional"))
    )
    (net (code "41") (name "Net-(D12-C)") (class "Default")
      (node (ref "D12") (pin "3") (pinfunction "C_3") (pintype "passive"))
      (node (ref "R115") (pin "1") (pinfunction "1_1") (pintype "passive"))
      (node (ref "R117") (pin "1") (pinfunction "1_1") (pintype "passive"))
      (node (ref "R120") (pin "2") (pinfunction "2_2") (pintype "passive"))
    )
    (net (code "42") (name "Net-(D13-A)") (class "Default")
      (node (ref "D13") (pin "1") (pinfunction "A_1") (pintype "passive"))
      (node (ref "U$50") (pin "8") (pinfunction "OUTC_8") (pintype "bidirectional"))
    )
    (net (code "43") (name "Net-(D13-C)") (class "Default")
      (node (ref "D13") (pin "3") (pinfunction "C_3") (pintype "passive"))
      (node (ref "R125") (pin "1") (pinfunction "1_1") (pintype "passive"))
      (node (ref "R127") (pin "1") (pinfunction "1_1") (pintype "passive"))
      (node (ref "R130") (pin "2") (pinfunction "2_2") (pintype "passive"))
    )
    (net (code "44") (name "Net-(D14-A)") (class "Default")
      (node (ref "D14") (pin "1") (pinfunction "A_1") (pintype "passive"))
      (node (ref "U$54") (pin "8") (pinfunction "OUTC_8") (pintype "bidirectional"))
    )
    (net (code "45") (name "Net-(D14-C)") (class "Default")
      (node (ref "D14") (pin "3") (pinfunction "C_3") (pintype "passive"))
      (node (ref "R135") (pin "1") (pinfunction "1_1") (pintype "passive"))
      (node (ref "R137") (pin "1") (pinfunction "1_1") (pintype "passive"))
      (node (ref "R140") (pin "2") (pinfunction "2_2") (pintype "passive"))
    )
    (net (code "46") (name "Net-(U$1--IN)") (class "Default")
      (node (ref "U$1") (pin "3") (pinfunction "-IN_3") (pintype "bidirectional"))
      (node (ref "U$10") (pin "2") (pinfunction "IN-_2") (pintype "bidirectional"))
    )
    (net (code "47") (name "Net-(U$1-GSEN1)") (class "Default")
      (node (ref "R1") (pin "1") (pinfunction "1_1") (pintype "passive"))
      (node (ref "U$1") (pin "4") (pinfunction "GSEN1_4") (pintype "bidirectional"))
      (node (ref "U$1") (pin "5") (pinfunction "GSET1_5") (pintype "bidirectional"))
    )
    (net (code "48") (name "Net-(U$1-GSEN2)") (class "Default")
      (node (ref "R1") (pin "2") (pinfunction "2_2") (pintype "passive"))
      (node (ref "U$1") (pin "12") (pinfunction "GSET2_12") (pintype "bidirectional"))
      (node (ref "U$1") (pin "13") (pinfunction "GSEN2_13") (pintype "bidirectional"))
    )
    (net (code "49") (name "Net-(U$1-IN+)") (class "Default")
      (node (ref "U$1") (pin "14") (pinfunction "IN+_14") (pintype "bidirectional"))
      (node (ref "U$10") (pin "1") (pinfunction "IN+_1") (pintype "bidirectional"))
    )
    (net (code "50") (name "Net-(U$1-OUT)") (class "Default")
      (node (ref "R2") (pin "1") (pinfunction "1_1") (pintype "passive"))
      (node (ref "U$1") (pin "1") (pinfunction "OUT_1") (pintype "bidirectional"))
    )
    (net (code "51") (name "Net-(U$2-INA-)") (class "Default")
      (node (ref "R2") (pin "2") (pinfunction "2_2") (pintype "passive"))
      (node (ref "U$2") (pin "2") (pinfunction "INA-_2") (pintype "bidirectional"))
      (node (ref "U$3") (pin "1") (pinfunction "1_1") (pintype "bidirectional"))
    )
    (net (code "52") (name "Net-(U$2-INB+)") (class "Default")
      (node (ref "C3") (pin "2") (pinfunction "2_2") (pintype "passive"))
      (node (ref "R3") (pin "2") (pinfunction "2_2") (pintype "passive"))
      (node (ref "U$2") (pin "5") (pinfunction "INB+_5") (pintype "bidirectional"))
    )
    (net (code "53") (name "Net-(U$2-INB-)") (class "Default")
      (node (ref "R4") (pin "1") (pinfunction "1_1") (pintype "passive"))
      (node (ref "U$2") (pin "6") (pinfunction "INB-_6") (pintype "bidirectional"))
      (node (ref "U$2") (pin "7") (pinfunction "OUTB_7") (pintype "bidirectional"))
    )
    (net (code "54") (name "Net-(U$2-INC-)") (class "Default")
      (node (ref "R10") (pin "1") (pinfunction "1_1") (pintype "passive"))
      (node (ref "R4") (pin "2") (pinfunction "2_2") (pintype "passive"))
      (node (ref "U$2") (pin "9") (pinfunction "INC-_9") (pintype "bidirectional"))
    )
    (net (code "55") (name "Net-(U$2-IND+)") (class "Default")
      (node (ref "C6") (pin "1") (pinfunction "1_1") (pintype "passive"))
      (node (ref "R6") (pin "1") (pinfunction "1_1") (pintype "passive"))
      (node (ref "U$2") (pin "12") (pinfunction "IND+_12") (pintype "bidirectional"))
    )
    (net (code "56") (name "Net-(U$2-IND-)") (class "Default")
      (node (ref "R8") (pin "1") (pinfunction "1_1") (pintype "passive"))
      (node (ref "R9") (pin "1") (pinfunction "1_1") (pintype "passive"))
      (node (ref "U$2") (pin "13") (pinfunction "IND-_13") (pintype "bidirectional"))
    )
    (net (code "57") (name "Net-(U$2-OUTA)") (class "Default")
      (node (ref "C3") (pin "1") (pinfunction "1_1") (pintype "passive"))
      (node (ref "U$2") (pin "1") (pinfunction "OUTA_1") (pintype "bidirectional"))
      (node (ref "U$3") (pin "2") (pinfunction "2_2") (pintype "bidirectional"))
    )
    (net (code "58") (name "Net-(U$2-OUTD)") (class "Default")
      (node (ref "C7") (pin "2") (pinfunction "2_2") (pintype "passive"))
      (node (ref "R9") (pin "2") (pinfunction "2_2") (pintype "passive"))
      (node (ref "U$2") (pin "14") (pinfunction "OUTD_14") (pintype "bidirectional"))
      (node (ref "U$58") (pin "14") (pinfunction "14_14") (pintype "bidirectional"))
    )
    (net (code "59") (name "Net-(U$4--IN)") (class "Default")
      (node (ref "U$4") (pin "3") (pinfunction "-IN_3") (pintype "bidirectional"))
      (node (ref "U$7") (pin "2") (pinfunction "IN-_2") (pintype "bidirectional"))
    )
    (net (code "60") (name "Net-(U$4-GSEN1)") (class "Default")
      (node (ref "R11") (pin "1") (pinfunction "1_1") (pintype "passive"))
      (node (ref "U$4") (pin "4") (pinfunction "GSEN1_4") (pintype "bidirectional"))
      (node (ref "U$4") (pin "5") (pinfunction "GSET1_5") (pintype "bidirectional"))
    )
    (net (code "61") (name "Net-(U$4-GSEN2)") (class "Default")
      (node (ref "R11") (pin "2") (pinfunction "2_2") (pintype "passive"))
      (node (ref "U$4") (pin "12") (pinfunction "GSET2_12") (pintype "bidirectional"))
      (node (ref "U$4") (pin "13") (pinfunction "GSEN2_13") (pintype "bidirectional"))
    )
    (net (code "62") (name "Net-(U$4-IN+)") (class "Default")
      (node (ref "U$4") (pin "14") (pinfunction "IN+_14") (pintype "bidirectional"))
      (node (ref "U$7") (pin "1") (pinfunction "IN+_1") (pintype "bidirectional"))
    )
    (net (code "63") (name "Net-(U$4-OUT)") (class "Default")
      (node (ref "R12") (pin "1") (pinfunction "1_1") (pintype "passive"))
      (node (ref "U$4") (pin "1") (pinfunction "OUT_1") (pintype "bidirectional"))
    )
    (net (code "64") (name "Net-(U$5-INA-)") (class "Default")
      (node (ref "R12") (pin "2") (pinfunction "2_2") (pintype "passive"))
      (node (ref "U$5") (pin "2") (pinfunction "INA-_2") (pintype "bidirectional"))
      (node (ref "U$6") (pin "1") (pinfunction "1_1") (pintype "bidirectional"))
    )
    (net (code "65") (name "Net-(U$5-INB+)") (class "Default")
      (node (ref "C10") (pin "2") (pinfunction "2_2") (pintype "passive"))
      (node (ref "R13") (pin "2") (pinfunction "2_2") (pintype "passive"))
      (node (ref "U$5") (pin "5") (pinfunction "INB+_5") (pintype "bidirectional"))
    )
    (net (code "66") (name "Net-(U$5-INB-)") (class "Default")
      (node (ref "R14") (pin "1") (pinfunction "1_1") (pintype "passive"))
      (node (ref "U$5") (pin "6") (pinfunction "INB-_6") (pintype "bidirectional"))
      (node (ref "U$5") (pin "7") (pinfunction "OUTB_7") (pintype "bidirectional"))
    )
    (net (code "67") (name "Net-(U$5-INC-)") (class "Default")
      (node (ref "R14") (pin "2") (pinfunction "2_2") (pintype "passive"))
      (node (ref "R20") (pin "1") (pinfunction "1_1") (pintype "passive"))
      (node (ref "U$5") (pin "9") (pinfunction "INC-_9") (pintype "bidirectional"))
    )
    (net (code "68") (name "Net-(U$5-IND+)") (class "Default")
      (node (ref "C13") (pin "1") (pinfunction "1_1") (pintype "passive"))
      (node (ref "R16") (pin "1") (pinfunction "1_1") (pintype "passive"))
      (node (ref "U$5") (pin "12") (pinfunction "IND+_12") (pintype "bidirectional"))
    )
    (net (code "69") (name "Net-(U$5-IND-)") (class "Default")
      (node (ref "R18") (pin "1") (pinfunction "1_1") (pintype "passive"))
      (node (ref "R19") (pin "1") (pinfunction "1_1") (pintype "passive"))
      (node (ref "U$5") (pin "13") (pinfunction "IND-_13") (pintype "bidirectional"))
    )
    (net (code "70") (name "Net-(U$5-OUTA)") (class "Default")
      (node (ref "C10") (pin "1") (pinfunction "1_1") (pintype "passive"))
      (node (ref "U$5") (pin "1") (pinfunction "OUTA_1") (pintype "bidirectional"))
      (node (ref "U$6") (pin "2") (pinfunction "2_2") (pintype "bidirectional"))
    )
    (net (code "71") (name "Net-(U$5-OUTD)") (class "Default")
      (node (ref "C14") (pin "2") (pinfunction "2_2") (pintype "passive"))
      (node (ref "R19") (pin "2") (pinfunction "2_2") (pintype "passive"))
      (node (ref "U$5") (pin "14") (pinfunction "OUTD_14") (pintype "bidirectional"))
      (node (ref "U$58") (pin "13") (pinfunction "13_13") (pintype "bidirectional"))
    )
    (net (code "72") (name "Net-(U$8-GSEN1)") (class "Default")
      (node (ref "R21") (pin "1") (pinfunction "1_1") (pintype "passive"))
      (node (ref "U$8") (pin "4") (pinfunction "GSEN1_4") (pintype "bidirectional"))
      (node (ref "U$8") (pin "5") (pinfunction "GSET1_5") (pintype "bidirectional"))
    )
    (net (code "73") (name "Net-(U$8-GSEN2)") (class "Default")
      (node (ref "R21") (pin "2") (pinfunction "2_2") (pintype "passive"))
      (node (ref "U$8") (pin "12") (pinfunction "GSET2_12") (pintype "bidirectional"))
      (node (ref "U$8") (pin "13") (pinfunction "GSEN2_13") (pintype "bidirectional"))
    )
    (net (code "74") (name "Net-(U$8-OUT)") (class "Default")
      (node (ref "R22") (pin "1") (pinfunction "1_1") (pintype "passive"))
      (node (ref "U$8") (pin "1") (pinfunction "OUT_1") (pintype "bidirectional"))
    )
    (net (code "75") (name "Net-(U$9-INA-)") (class "Default")
      (node (ref "R22") (pin "2") (pinfunction "2_2") (pintype "passive"))
      (node (ref "U$11") (pin "1") (pinfunction "1_1") (pintype "bidirectional"))
      (node (ref "U$9") (pin "2") (pinfunction "INA-_2") (pintype "bidirectional"))
    )
    (net (code "76") (name "Net-(U$9-INB+)") (class "Default")
      (node (ref "C17") (pin "2") (pinfunction "2_2") (pintype "passive"))
      (node (ref "R23") (pin "2") (pinfunction "2_2") (pintype "passive"))
      (node (ref "U$9") (pin "5") (pinfunction "INB+_5") (pintype "bidirectional"))
    )
    (net (code "77") (name "Net-(U$9-INB-)") (class "Default")
      (node (ref "R24") (pin "1") (pinfunction "1_1") (pintype "passive"))
      (node (ref "U$9") (pin "6") (pinfunction "INB-_6") (pintype "bidirectional"))
      (node (ref "U$9") (pin "7") (pinfunction "OUTB_7") (pintype "bidirectional"))
    )
    (net (code "78") (name "Net-(U$9-INC-)") (class "Default")
      (node (ref "R24") (pin "2") (pinfunction "2_2") (pintype "passive"))
      (node (ref "R30") (pin "1") (pinfunction "1_1") (pintype "passive"))
      (node (ref "U$9") (pin "9") (pinfunction "INC-_9") (pintype "bidirectional"))
    )
    (net (code "79") (name "Net-(U$9-IND+)") (class "Default")
      (node (ref "C20") (pin "1") (pinfunction "1_1") (pintype "passive"))
      (node (ref "R26") (pin "1") (pinfunction "1_1") (pintype "passive"))
      (node (ref "U$9") (pin "12") (pinfunction "IND+_12") (pintype "bidirectional"))
    )
    (net (code "80") (name "Net-(U$9-IND-)") (class "Default")
      (node (ref "R28") (pin "1") (pinfunction "1_1") (pintype "passive"))
      (node (ref "R29") (pin "1") (pinfunction "1_1") (pintype "passive"))
      (node (ref "U$9") (pin "13") (pinfunction "IND-_13") (pintype "bidirectional"))
    )
    (net (code "81") (name "Net-(U$9-OUTA)") (class "Default")
      (node (ref "C17") (pin "1") (pinfunction "1_1") (pintype "passive"))
      (node (ref "U$11") (pin "2") (pinfunction "2_2") (pintype "bidirectional"))
      (node (ref "U$9") (pin "1") (pinfunction "OUTA_1") (pintype "bidirectional"))
    )
    (net (code "82") (name "Net-(U$9-OUTD)") (class "Default")
      (node (ref "C21") (pin "2") (pinfunction "2_2") (pintype "passive"))
      (node (ref "R29") (pin "2") (pinfunction "2_2") (pintype "passive"))
      (node (ref "U$58") (pin "12") (pinfunction "12_12") (pintype "bidirectional"))
      (node (ref "U$9") (pin "14") (pinfunction "OUTD_14") (pintype "bidirectional"))
    )
    (net (code "83") (name "Net-(U$12-IN+)") (class "Default")
      (node (ref "U$12") (pin "1") (pinfunction "IN+_1") (pintype "bidirectional"))
      (node (ref "U$8") (pin "14") (pinfunction "IN+_14") (pintype "bidirectional"))
    )
    (net (code "84") (name "Net-(U$12-IN-)") (class "Default")
      (node (ref "U$12") (pin "2") (pinfunction "IN-_2") (pintype "bidirectional"))
      (node (ref "U$8") (pin "3") (pinfunction "-IN_3") (pintype "bidirectional"))
    )
    (net (code "85") (name "Net-(U$13--IN)") (class "Default")
      (node (ref "U$13") (pin "3") (pinfunction "-IN_3") (pintype "bidirectional"))
      (node (ref "U$16") (pin "2") (pinfunction "IN-_2") (pintype "bidirectional"))
    )
    (net (code "86") (name "Net-(U$13-GSEN1)") (class "Default")
      (node (ref "R31") (pin "1") (pinfunction "1_1") (pintype "passive"))
      (node (ref "U$13") (pin "4") (pinfunction "GSEN1_4") (pintype "bidirectional"))
      (node (ref "U$13") (pin "5") (pinfunction "GSET1_5") (pintype "bidirectional"))
    )
    (net (code "87") (name "Net-(U$13-GSEN2)") (class "Default")
      (node (ref "R31") (pin "2") (pinfunction "2_2") (pintype "passive"))
      (node (ref "U$13") (pin "12") (pinfunction "GSET2_12") (pintype "bidirectional"))
      (node (ref "U$13") (pin "13") (pinfunction "GSEN2_13") (pintype "bidirectional"))
    )
    (net (code "88") (name "Net-(U$13-IN+)") (class "Default")
      (node (ref "U$13") (pin "14") (pinfunction "IN+_14") (pintype "bidirectional"))
      (node (ref "U$16") (pin "1") (pinfunction "IN+_1") (pintype "bidirectional"))
    )
    (net (code "89") (name "Net-(U$13-OUT)") (class "Default")
      (node (ref "R32") (pin "1") (pinfunction "1_1") (pintype "passive"))
      (node (ref "U$13") (pin "1") (pinfunction "OUT_1") (pintype "bidirectional"))
    )
    (net (code "90") (name "Net-(U$14-INA-)") (class "Default")
      (node (ref "R32") (pin "2") (pinfunction "2_2") (pintype "passive"))
      (node (ref "U$14") (pin "2") (pinfunction "INA-_2") (pintype "bidirectional"))
      (node (ref "U$15") (pin "1") (pinfunction "1_1") (pintype "bidirectional"))
    )
    (net (code "91") (name "Net-(U$14-INB+)") (class "Default")
      (node (ref "C24") (pin "2") (pinfunction "2_2") (pintype "passive"))
      (node (ref "R33") (pin "2") (pinfunction "2_2") (pintype "passive"))
      (node (ref "U$14") (pin "5") (pinfunction "INB+_5") (pintype "bidirectional"))
    )
    (net (code "92") (name "Net-(U$14-INB-)") (class "Default")
      (node (ref "R34") (pin "1") (pinfunction "1_1") (pintype "passive"))
      (node (ref "U$14") (pin "6") (pinfunction "INB-_6") (pintype "bidirectional"))
      (node (ref "U$14") (pin "7") (pinfunction "OUTB_7") (pintype "bidirectional"))
    )
    (net (code "93") (name "Net-(U$14-INC-)") (class "Default")
      (node (ref "R34") (pin "2") (pinfunction "2_2") (pintype "passive"))
      (node (ref "R40") (pin "1") (pinfunction "1_1") (pintype "passive"))
      (node (ref "U$14") (pin "9") (pinfunction "INC-_9") (pintype "bidirectional"))
    )
    (net (code "94") (name "Net-(U$14-IND+)") (class "Default")
      (node (ref "C27") (pin "1") (pinfunction "1_1") (pintype "passive"))
      (node (ref "R36") (pin "1") (pinfunction "1_1") (pintype "passive"))
      (node (ref "U$14") (pin "12") (pinfunction "IND+_12") (pintype "bidirectional"))
    )
    (net (code "95") (name "Net-(U$14-IND-)") (class "Default")
      (node (ref "R38") (pin "1") (pinfunction "1_1") (pintype "passive"))
      (node (ref "R39") (pin "1") (pinfunction "1_1") (pintype "passive"))
      (node (ref "U$14") (pin "13") (pinfunction "IND-_13") (pintype "bidirectional"))
    )
    (net (code "96") (name "Net-(U$14-OUTA)") (class "Default")
      (node (ref "C24") (pin "1") (pinfunction "1_1") (pintype "passive"))
      (node (ref "U$14") (pin "1") (pinfunction "OUTA_1") (pintype "bidirectional"))
      (node (ref "U$15") (pin "2") (pinfunction "2_2") (pintype "bidirectional"))
    )
    (net (code "97") (name "Net-(U$14-OUTD)") (class "Default")
      (node (ref "C28") (pin "2") (pinfunction "2_2") (pintype "passive"))
      (node (ref "R39") (pin "2") (pinfunction "2_2") (pintype "passive"))
      (node (ref "U$14") (pin "14") (pinfunction "OUTD_14") (pintype "bidirectional"))
      (node (ref "U$58") (pin "11") (pinfunction "11_11") (pintype "bidirectional"))
    )
    (net (code "98") (name "Net-(U$17--IN)") (class "Default")
      (node (ref "U$17") (pin "3") (pinfunction "-IN_3") (pintype "bidirectional"))
      (node (ref "U$20") (pin "2") (pinfunction "IN-_2") (pintype "bidirectional"))
    )
    (net (code "99") (name "Net-(U$17-GSEN1)") (class "Default")
      (node (ref "R41") (pin "1") (pinfunction "1_1") (pintype "passive"))
      (node (ref "U$17") (pin "4") (pinfunction "GSEN1_4") (pintype "bidirectional"))
      (node (ref "U$17") (pin "5") (pinfunction "GSET1_5") (pintype "bidirectional"))
    )
    (net (code "100") (name "Net-(U$17-GSEN2)") (class "Default")
      (node (ref "R41") (pin "2") (pinfunction "2_2") (pintype "passive"))
      (node (ref "U$17") (pin "12") (pinfunction "GSET2_12") (pintype "bidirectional"))
      (node (ref "U$17") (pin "13") (pinfunction "GSEN2_13") (pintype "bidirectional"))
    )
    (net (code "101") (name "Net-(U$17-IN+)") (class "Default")
      (node (ref "U$17") (pin "14") (pinfunction "IN+_14") (pintype "bidirectional"))
      (node (ref "U$20") (pin "1") (pinfunction "IN+_1") (pintype "bidirectional"))
    )
    (net (code "102") (name "Net-(U$17-OUT)") (class "Default")
      (node (ref "R42") (pin "1") (pinfunction "1_1") (pintype "passive"))
      (node (ref "U$17") (pin "1") (pinfunction "OUT_1") (pintype "bidirectional"))
    )
    (net (code "103") (name "Net-(U$18-INA-)") (class "Default")
      (node (ref "R42") (pin "2") (pinfunction "2_2") (pintype "passive"))
      (node (ref "U$18") (pin "2") (pinfunction "INA-_2") (pintype "bidirectional"))
      (node (ref "U$19") (pin "1") (pinfunction "1_1") (pintype "bidirectional"))
    )
    (net (code "104") (name "Net-(U$18-INB+)") (class "Default")
      (node (ref "C31") (pin "2") (pinfunction "2_2") (pintype "passive"))
      (node (ref "R43") (pin "2") (pinfunction "2_2") (pintype "passive"))
      (node (ref "U$18") (pin "5") (pinfunction "INB+_5") (pintype "bidirectional"))
    )
    (net (code "105") (name "Net-(U$18-INB-)") (class "Default")
      (node (ref "R44") (pin "1") (pinfunction "1_1") (pintype "passive"))
      (node (ref "U$18") (pin "6") (pinfunction "INB-_6") (pintype "bidirectional"))
      (node (ref "U$18") (pin "7") (pinfunction "OUTB_7") (pintype "bidirectional"))
    )
    (net (code "106") (name "Net-(U$18-INC-)") (class "Default")
      (node (ref "R44") (pin "2") (pinfunction "2_2") (pintype "passive"))
      (node (ref "R50") (pin "1") (pinfunction "1_1") (pintype "passive"))
      (node (ref "U$18") (pin "9") (pinfunction "INC-_9") (pintype "bidirectional"))
    )
    (net (code "107") (name "Net-(U$18-IND+)") (class "Default")
      (node (ref "C34") (pin "1") (pinfunction "1_1") (pintype "passive"))
      (node (ref "R46") (pin "1") (pinfunction "1_1") (pintype "passive"))
      (node (ref "U$18") (pin "12") (pinfunction "IND+_12") (pintype "bidirectional"))
    )
    (net (code "108") (name "Net-(U$18-IND-)") (class "Default")
      (node (ref "R48") (pin "1") (pinfunction "1_1") (pintype "passive"))
      (node (ref "R49") (pin "1") (pinfunction "1_1") (pintype "passive"))
      (node (ref "U$18") (pin "13") (pinfunction "IND-_13") (pintype "bidirectional"))
    )
    (net (code "109") (name "Net-(U$18-OUTA)") (class "Default")
      (node (ref "C31") (pin "1") (pinfunction "1_1") (pintype "passive"))
      (node (ref "U$18") (pin "1") (pinfunction "OUTA_1") (pintype "bidirectional"))
      (node (ref "U$19") (pin "2") (pinfunction "2_2") (pintype "bidirectional"))
    )
    (net (code "110") (name "Net-(U$18-OUTD)") (class "Default")
      (node (ref "C35") (pin "2") (pinfunction "2_2") (pintype "passive"))
      (node (ref "R49") (pin "2") (pinfunction "2_2") (pintype "passive"))
      (node (ref "U$18") (pin "14") (pinfunction "OUTD_14") (pintype "bidirectional"))
      (node (ref "U$58") (pin "10") (pinfunction "10_10") (pintype "bidirectional"))
    )
    (net (code "111") (name "Net-(U$21--IN)") (class "Default")
      (node (ref "U$21") (pin "3") (pinfunction "-IN_3") (pintype "bidirectional"))
      (node (ref "U$24") (pin "2") (pinfunction "IN-_2") (pintype "bidirectional"))
    )
    (net (code "112") (name "Net-(U$21-GSEN1)") (class "Default")
      (node (ref "R51") (pin "1") (pinfunction "1_1") (pintype "passive"))
      (node (ref "U$21") (pin "4") (pinfunction "GSEN1_4") (pintype "bidirectional"))
      (node (ref "U$21") (pin "5") (pinfunction "GSET1_5") (pintype "bidirectional"))
    )
    (net (code "113") (name "Net-(U$21-GSEN2)") (class "Default")
      (node (ref "R51") (pin "2") (pinfunction "2_2") (pintype "passive"))
      (node (ref "U$21") (pin "12") (pinfunction "GSET2_12") (pintype "bidirectional"))
      (node (ref "U$21") (pin "13") (pinfunction "GSEN2_13") (pintype "bidirectional"))
    )
    (net (code "114") (name "Net-(U$21-IN+)") (class "Default")
      (node (ref "U$21") (pin "14") (pinfunction "IN+_14") (pintype "bidirectional"))
      (node (ref "U$24") (pin "1") (pinfunction "IN+_1") (pintype "bidirectional"))
    )
    (net (code "115") (name "Net-(U$21-OUT)") (class "Default")
      (node (ref "R52") (pin "1") (pinfunction "1_1") (pintype "passive"))
      (node (ref "U$21") (pin "1") (pinfunction "OUT_1") (pintype "bidirectional"))
    )
    (net (code "116") (name "Net-(U$22-INA-)") (class "Default")
      (node (ref "R52") (pin "2") (pinfunction "2_2") (pintype "passive"))
      (node (ref "U$22") (pin "2") (pinfunction "INA-_2") (pintype "bidirectional"))
      (node (ref "U$23") (pin "1") (pinfunction "1_1") (pintype "bidirectional"))
    )
    (net (code "117") (name "Net-(U$22-INB+)") (class "Default")
      (node (ref "C38") (pin "2") (pinfunction "2_2") (pintype "passive"))
      (node (ref "R53") (pin "2") (pinfunction "2_2") (pintype "passive"))
      (node (ref "U$22") (pin "5") (pinfunction "INB+_5") (pintype "bidirectional"))
    )
    (net (code "118") (name "Net-(U$22-INB-)") (class "Default")
      (node (ref "R54") (pin "1") (pinfunction "1_1") (pintype "passive"))
      (node (ref "U$22") (pin "6") (pinfunction "INB-_6") (pintype "bidirectional"))
      (node (ref "U$22") (pin "7") (pinfunction "OUTB_7") (pintype "bidirectional"))
    )
    (net (code "119") (name "Net-(U$22-INC-)") (class "Default")
      (node (ref "R54") (pin "2") (pinfunction "2_2") (pintype "passive"))
      (node (ref "R60") (pin "1") (pinfunction "1_1") (pintype "passive"))
      (node (ref "U$22") (pin "9") (pinfunction "INC-_9") (pintype "bidirectional"))
    )
    (net (code "120") (name "Net-(U$22-IND+)") (class "Default")
      (node (ref "C41") (pin "1") (pinfunction "1_1") (pintype "passive"))
      (node (ref "R56") (pin "1") (pinfunction "1_1") (pintype "passive"))
      (node (ref "U$22") (pin "12") (pinfunction "IND+_12") (pintype "bidirectional"))
    )
    (net (code "121") (name "Net-(U$22-IND-)") (class "Default")
      (node (ref "R58") (pin "1") (pinfunction "1_1") (pintype "passive"))
      (node (ref "R59") (pin "1") (pinfunction "1_1") (pintype "passive"))
      (node (ref "U$22") (pin "13") (pinfunction "IND-_13") (pintype "bidirectional"))
    )
    (net (code "122") (name "Net-(U$22-OUTA)") (class "Default")
      (node (ref "C38") (pin "1") (pinfunction "1_1") (pintype "passive"))
      (node (ref "U$22") (pin "1") (pinfunction "OUTA_1") (pintype "bidirectional"))
      (node (ref "U$23") (pin "2") (pinfunction "2_2") (pintype "bidirectional"))
    )
    (net (code "123") (name "Net-(U$22-OUTD)") (class "Default")
      (node (ref "C42") (pin "2") (pinfunction "2_2") (pintype "passive"))
      (node (ref "R59") (pin "2") (pinfunction "2_2") (pintype "passive"))
      (node (ref "U$22") (pin "14") (pinfunction "OUTD_14") (pintype "bidirectional"))
      (node (ref "U$58") (pin "9") (pinfunction "9_9") (pintype "bidirectional"))
    )
    (net (code "124") (name "Net-(U$25--IN)") (class "Default")
      (node (ref "U$25") (pin "3") (pinfunction "-IN_3") (pintype "bidirectional"))
      (node (ref "U$28") (pin "2") (pinfunction "IN-_2") (pintype "bidirectional"))
    )
    (net (code "125") (name "Net-(U$25-GSEN1)") (class "Default")
      (node (ref "R61") (pin "1") (pinfunction "1_1") (pintype "passive"))
      (node (ref "U$25") (pin "4") (pinfunction "GSEN1_4") (pintype "bidirectional"))
      (node (ref "U$25") (pin "5") (pinfunction "GSET1_5") (pintype "bidirectional"))
    )
    (net (code "126") (name "Net-(U$25-GSEN2)") (class "Default")
      (node (ref "R61") (pin "2") (pinfunction "2_2") (pintype "passive"))
      (node (ref "U$25") (pin "12") (pinfunction "GSET2_12") (pintype "bidirectional"))
      (node (ref "U$25") (pin "13") (pinfunction "GSEN2_13") (pintype "bidirectional"))
    )
    (net (code "127") (name "Net-(U$25-IN+)") (class "Default")
      (node (ref "U$25") (pin "14") (pinfunction "IN+_14") (pintype "bidirectional"))
      (node (ref "U$28") (pin "1") (pinfunction "IN+_1") (pintype "bidirectional"))
    )
    (net (code "128") (name "Net-(U$25-OUT)") (class "Default")
      (node (ref "R62") (pin "1") (pinfunction "1_1") (pintype "passive"))
      (node (ref "U$25") (pin "1") (pinfunction "OUT_1") (pintype "bidirectional"))
    )
    (net (code "129") (name "Net-(U$26-INA-)") (class "Default")
      (node (ref "R62") (pin "2") (pinfunction "2_2") (pintype "passive"))
      (node (ref "U$26") (pin "2") (pinfunction "INA-_2") (pintype "bidirectional"))
      (node (ref "U$27") (pin "1") (pinfunction "1_1") (pintype "bidirectional"))
    )
    (net (code "130") (name "Net-(U$26-INB+)") (class "Default")
      (node (ref "C45") (pin "2") (pinfunction "2_2") (pintype "passive"))
      (node (ref "R63") (pin "2") (pinfunction "2_2") (pintype "passive"))
      (node (ref "U$26") (pin "5") (pinfunction "INB+_5") (pintype "bidirectional"))
    )
    (net (code "131") (name "Net-(U$26-INB-)") (class "Default")
      (node (ref "R64") (pin "1") (pinfunction "1_1") (pintype "passive"))
      (node (ref "U$26") (pin "6") (pinfunction "INB-_6") (pintype "bidirectional"))
      (node (ref "U$26") (pin "7") (pinfunction "OUTB_7") (pintype "bidirectional"))
    )
    (net (code "132") (name "Net-(U$26-INC-)") (class "Default")
      (node (ref "R64") (pin "2") (pinfunction "2_2") (pintype "passive"))
      (node (ref "R70") (pin "1") (pinfunction "1_1") (pintype "passive"))
      (node (ref "U$26") (pin "9") (pinfunction "INC-_9") (pintype "bidirectional"))
    )
    (net (code "133") (name "Net-(U$26-IND+)") (class "Default")
      (node (ref "C48") (pin "1") (pinfunction "1_1") (pintype "passive"))
      (node (ref "R66") (pin "1") (pinfunction "1_1") (pintype "passive"))
      (node (ref "U$26") (pin "12") (pinfunction "IND+_12") (pintype "bidirectional"))
    )
    (net (code "134") (name "Net-(U$26-IND-)") (class "Default")
      (node (ref "R68") (pin "1") (pinfunction "1_1") (pintype "passive"))
      (node (ref "R69") (pin "1") (pinfunction "1_1") (pintype "passive"))
      (node (ref "U$26") (pin "13") (pinfunction "IND-_13") (pintype "bidirectional"))
    )
    (net (code "135") (name "Net-(U$26-OUTA)") (class "Default")
      (node (ref "C45") (pin "1") (pinfunction "1_1") (pintype "passive"))
      (node (ref "U$26") (pin "1") (pinfunction "OUTA_1") (pintype "bidirectional"))
      (node (ref "U$27") (pin "2") (pinfunction "2_2") (pintype "bidirectional"))
    )
    (net (code "136") (name "Net-(U$26-OUTD)") (class "Default")
      (node (ref "C49") (pin "2") (pinfunction "2_2") (pintype "passive"))
      (node (ref "R69") (pin "2") (pinfunction "2_2") (pintype "passive"))
      (node (ref "U$26") (pin "14") (pinfunction "OUTD_14") (pintype "bidirectional"))
      (node (ref "U$58") (pin "8") (pinfunction "8_8") (pintype "bidirectional"))
    )
    (net (code "137") (name "Net-(U$29--IN)") (class "Default")
      (node (ref "U$29") (pin "3") (pinfunction "-IN_3") (pintype "bidirectional"))
      (node (ref "U$32") (pin "2") (pinfunction "IN-_2") (pintype "bidirectional"))
    )
    (net (code "138") (name "Net-(U$29-GSEN1)") (class "Default")
      (node (ref "R71") (pin "1") (pinfunction "1_1") (pintype "passive"))
      (node (ref "U$29") (pin "4") (pinfunction "GSEN1_4") (pintype "bidirectional"))
      (node (ref "U$29") (pin "5") (pinfunction "GSET1_5") (pintype "bidirectional"))
    )
    (net (code "139") (name "Net-(U$29-GSEN2)") (class "Default")
      (node (ref "R71") (pin "2") (pinfunction "2_2") (pintype "passive"))
      (node (ref "U$29") (pin "12") (pinfunction "GSET2_12") (pintype "bidirectional"))
      (node (ref "U$29") (pin "13") (pinfunction "GSEN2_13") (pintype "bidirectional"))
    )
    (net (code "140") (name "Net-(U$29-IN+)") (class "Default")
      (node (ref "U$29") (pin "14") (pinfunction "IN+_14") (pintype "bidirectional"))
      (node (ref "U$32") (pin "1") (pinfunction "IN+_1") (pintype "bidirectional"))
    )
    (net (code "141") (name "Net-(U$29-OUT)") (class "Default")
      (node (ref "R72") (pin "1") (pinfunction "1_1") (pintype "passive"))
      (node (ref "U$29") (pin "1") (pinfunction "OUT_1") (pintype "bidirectional"))
    )
    (net (code "142") (name "Net-(U$30-INA-)") (class "Default")
      (node (ref "R72") (pin "2") (pinfunction "2_2") (pintype "passive"))
      (node (ref "U$30") (pin "2") (pinfunction "INA-_2") (pintype "bidirectional"))
      (node (ref "U$31") (pin "1") (pinfunction "1_1") (pintype "bidirectional"))
    )
    (net (code "143") (name "Net-(U$30-INB+)") (class "Default")
      (node (ref "C52") (pin "2") (pinfunction "2_2") (pintype "passive"))
      (node (ref "R73") (pin "2") (pinfunction "2_2") (pintype "passive"))
      (node (ref "U$30") (pin "5") (pinfunction "INB+_5") (pintype "bidirectional"))
    )
    (net (code "144") (name "Net-(U$30-INB-)") (class "Default")
      (node (ref "R74") (pin "1") (pinfunction "1_1") (pintype "passive"))
      (node (ref "U$30") (pin "6") (pinfunction "INB-_6") (pintype "bidirectional"))
      (node (ref "U$30") (pin "7") (pinfunction "OUTB_7") (pintype "bidirectional"))
    )
    (net (code "145") (name "Net-(U$30-INC-)") (class "Default")
      (node (ref "R74") (pin "2") (pinfunction "2_2") (pintype "passive"))
      (node (ref "R80") (pin "1") (pinfunction "1_1") (pintype "passive"))
      (node (ref "U$30") (pin "9") (pinfunction "INC-_9") (pintype "bidirectional"))
    )
    (net (code "146") (name "Net-(U$30-IND+)") (class "Default")
      (node (ref "C55") (pin "1") (pinfunction "1_1") (pintype "passive"))
      (node (ref "R76") (pin "1") (pinfunction "1_1") (pintype "passive"))
      (node (ref "U$30") (pin "12") (pinfunction "IND+_12") (pintype "bidirectional"))
    )
    (net (code "147") (name "Net-(U$30-IND-)") (class "Default")
      (node (ref "R78") (pin "1") (pinfunction "1_1") (pintype "passive"))
      (node (ref "R79") (pin "1") (pinfunction "1_1") (pintype "passive"))
      (node (ref "U$30") (pin "13") (pinfunction "IND-_13") (pintype "bidirectional"))
    )
    (net (code "148") (name "Net-(U$30-OUTA)") (class "Default")
      (node (ref "C52") (pin "1") (pinfunction "1_1") (pintype "passive"))
      (node (ref "U$30") (pin "1") (pinfunction "OUTA_1") (pintype "bidirectional"))
      (node (ref "U$31") (pin "2") (pinfunction "2_2") (pintype "bidirectional"))
    )
    (net (code "149") (name "Net-(U$30-OUTD)") (class "Default")
      (node (ref "C56") (pin "2") (pinfunction "2_2") (pintype "passive"))
      (node (ref "R79") (pin "2") (pinfunction "2_2") (pintype "passive"))
      (node (ref "U$30") (pin "14") (pinfunction "OUTD_14") (pintype "bidirectional"))
      (node (ref "U$58") (pin "7") (pinfunction "7_7") (pintype "bidirectional"))
    )
    (net (code "150") (name "Net-(U$33--IN)") (class "Default")
      (node (ref "U$33") (pin "3") (pinfunction "-IN_3") (pintype "bidirectional"))
      (node (ref "U$36") (pin "2") (pinfunction "IN-_2") (pintype "bidirectional"))
    )
    (net (code "151") (name "Net-(U$33-GSEN1)") (class "Default")
      (node (ref "R81") (pin "1") (pinfunction "1_1") (pintype "passive"))
      (node (ref "U$33") (pin "4") (pinfunction "GSEN1_4") (pintype "bidirectional"))
      (node (ref "U$33") (pin "5") (pinfunction "GSET1_5") (pintype "bidirectional"))
    )
    (net (code "152") (name "Net-(U$33-GSEN2)") (class "Default")
      (node (ref "R81") (pin "2") (pinfunction "2_2") (pintype "passive"))
      (node (ref "U$33") (pin "12") (pinfunction "GSET2_12") (pintype "bidirectional"))
      (node (ref "U$33") (pin "13") (pinfunction "GSEN2_13") (pintype "bidirectional"))
    )
    (net (code "153") (name "Net-(U$33-IN+)") (class "Default")
      (node (ref "U$33") (pin "14") (pinfunction "IN+_14") (pintype "bidirectional"))
      (node (ref "U$36") (pin "1") (pinfunction "IN+_1") (pintype "bidirectional"))
    )
    (net (code "154") (name "Net-(U$33-OUT)") (class "Default")
      (node (ref "R82") (pin "1") (pinfunction "1_1") (pintype "passive"))
      (node (ref "U$33") (pin "1") (pinfunction "OUT_1") (pintype "bidirectional"))
    )
    (net (code "155") (name "Net-(U$34-INA-)") (class "Default")
      (node (ref "R82") (pin "2") (pinfunction "2_2") (pintype "passive"))
      (node (ref "U$34") (pin "2") (pinfunction "INA-_2") (pintype "bidirectional"))
      (node (ref "U$35") (pin "1") (pinfunction "1_1") (pintype "bidirectional"))
    )
    (net (code "156") (name "Net-(U$34-INB+)") (class "Default")
      (node (ref "C59") (pin "2") (pinfunction "2_2") (pintype "passive"))
      (node (ref "R83") (pin "2") (pinfunction "2_2") (pintype "passive"))
      (node (ref "U$34") (pin "5") (pinfunction "INB+_5") (pintype "bidirectional"))
    )
    (net (code "157") (name "Net-(U$34-INB-)") (class "Default")
      (node (ref "R84") (pin "1") (pinfunction "1_1") (pintype "passive"))
      (node (ref "U$34") (pin "6") (pinfunction "INB-_6") (pintype "bidirectional"))
      (node (ref "U$34") (pin "7") (pinfunction "OUTB_7") (pintype "bidirectional"))
    )
    (net (code "158") (name "Net-(U$34-INC-)") (class "Default")
      (node (ref "R84") (pin "2") (pinfunction "2_2") (pintype "passive"))
      (node (ref "R90") (pin "1") (pinfunction "1_1") (pintype "passive"))
      (node (ref "U$34") (pin "9") (pinfunction "INC-_9") (pintype "bidirectional"))
    )
    (net (code "159") (name "Net-(U$34-IND+)") (class "Default")
      (node (ref "C62") (pin "1") (pinfunction "1_1") (pintype "passive"))
      (node (ref "R86") (pin "1") (pinfunction "1_1") (pintype "passive"))
      (node (ref "U$34") (pin "12") (pinfunction "IND+_12") (pintype "bidirectional"))
    )
    (net (code "160") (name "Net-(U$34-IND-)") (class "Default")
      (node (ref "R88") (pin "1") (pinfunction "1_1") (pintype "passive"))
      (node (ref "R89") (pin "1") (pinfunction "1_1") (pintype "passive"))
      (node (ref "U$34") (pin "13") (pinfunction "IND-_13") (pintype "bidirectional"))
    )
    (net (code "161") (name "Net-(U$34-OUTA)") (class "Default")
      (node (ref "C59") (pin "1") (pinfunction "1_1") (pintype "passive"))
      (node (ref "U$34") (pin "1") (pinfunction "OUTA_1") (pintype "bidirectional"))
      (node (ref "U$35") (pin "2") (pinfunction "2_2") (pintype "bidirectional"))
    )
    (net (code "162") (name "Net-(U$34-OUTD)") (class "Default")
      (node (ref "C63") (pin "2") (pinfunction "2_2") (pintype "passive"))
      (node (ref "R89") (pin "2") (pinfunction "2_2") (pintype "passive"))
      (node (ref "U$34") (pin "14") (pinfunction "OUTD_14") (pintype "bidirectional"))
      (node (ref "U$58") (pin "6") (pinfunction "6_6") (pintype "bidirectional"))
    )
    (net (code "163") (name "Net-(U$37--IN)") (class "Default")
      (node (ref "U$37") (pin "3") (pinfunction "-IN_3") (pintype "bidirectional"))
      (node (ref "U$40") (pin "2") (pinfunction "IN-_2") (pintype "bidirectional"))
    )
    (net (code "164") (name "Net-(U$37-GSEN1)") (class "Default")
      (node (ref "R91") (pin "1") (pinfunction "1_1") (pintype "passive"))
      (node (ref "U$37") (pin "4") (pinfunction "GSEN1_4") (pintype "bidirectional"))
      (node (ref "U$37") (pin "5") (pinfunction "GSET1_5") (pintype "bidirectional"))
    )
    (net (code "165") (name "Net-(U$37-GSEN2)") (class "Default")
      (node (ref "R91") (pin "2") (pinfunction "2_2") (pintype "passive"))
      (node (ref "U$37") (pin "12") (pinfunction "GSET2_12") (pintype "bidirectional"))
      (node (ref "U$37") (pin "13") (pinfunction "GSEN2_13") (pintype "bidirectional"))
    )
    (net (code "166") (name "Net-(U$37-IN+)") (class "Default")
      (node (ref "U$37") (pin "14") (pinfunction "IN+_14") (pintype "bidirectional"))
      (node (ref "U$40") (pin "1") (pinfunction "IN+_1") (pintype "bidirectional"))
    )
    (net (code "167") (name "Net-(U$37-OUT)") (class "Default")
      (node (ref "R92") (pin "1") (pinfunction "1_1") (pintype "passive"))
      (node (ref "U$37") (pin "1") (pinfunction "OUT_1") (pintype "bidirectional"))
    )
    (net (code "168") (name "Net-(U$38-INA-)") (class "Default")
      (node (ref "R92") (pin "2") (pinfunction "2_2") (pintype "passive"))
      (node (ref "U$38") (pin "2") (pinfunction "INA-_2") (pintype "bidirectional"))
      (node (ref "U$39") (pin "1") (pinfunction "1_1") (pintype "bidirectional"))
    )
    (net (code "169") (name "Net-(U$38-INB+)") (class "Default")
      (node (ref "C66") (pin "2") (pinfunction "2_2") (pintype "passive"))
      (node (ref "R93") (pin "2") (pinfunction "2_2") (pintype "passive"))
      (node (ref "U$38") (pin "5") (pinfunction "INB+_5") (pintype "bidirectional"))
    )
    (net (code "170") (name "Net-(U$38-INB-)") (class "Default")
      (node (ref "R94") (pin "1") (pinfunction "1_1") (pintype "passive"))
      (node (ref "U$38") (pin "6") (pinfunction "INB-_6") (pintype "bidirectional"))
      (node (ref "U$38") (pin "7") (pinfunction "OUTB_7") (pintype "bidirectional"))
    )
    (net (code "171") (name "Net-(U$38-INC-)") (class "Default")
      (node (ref "R100") (pin "1") (pinfunction "1_1") (pintype "passive"))
      (node (ref "R94") (pin "2") (pinfunction "2_2") (pintype "passive"))
      (node (ref "U$38") (pin "9") (pinfunction "INC-_9") (pintype "bidirectional"))
    )
    (net (code "172") (name "Net-(U$38-IND+)") (class "Default")
      (node (ref "C69") (pin "1") (pinfunction "1_1") (pintype "passive"))
      (node (ref "R96") (pin "1") (pinfunction "1_1") (pintype "passive"))
      (node (ref "U$38") (pin "12") (pinfunction "IND+_12") (pintype "bidirectional"))
    )
    (net (code "173") (name "Net-(U$38-IND-)") (class "Default")
      (node (ref "R98") (pin "1") (pinfunction "1_1") (pintype "passive"))
      (node (ref "R99") (pin "1") (pinfunction "1_1") (pintype "passive"))
      (node (ref "U$38") (pin "13") (pinfunction "IND-_13") (pintype "bidirectional"))
    )
    (net (code "174") (name "Net-(U$38-OUTA)") (class "Default")
      (node (ref "C66") (pin "1") (pinfunction "1_1") (pintype "passive"))
      (node (ref "U$38") (pin "1") (pinfunction "OUTA_1") (pintype "bidirectional"))
      (node (ref "U$39") (pin "2") (pinfunction "2_2") (pintype "bidirectional"))
    )
    (net (code "175") (name "Net-(U$38-OUTD)") (class "Default")
      (node (ref "C70") (pin "2") (pinfunction "2_2") (pintype "passive"))
      (node (ref "R99") (pin "2") (pinfunction "2_2") (pintype "passive"))
      (node (ref "U$38") (pin "14") (pinfunction "OUTD_14") (pintype "bidirectional"))
      (node (ref "U$58") (pin "5") (pinfunction "5_5") (pintype "bidirectional"))
    )
    (net (code "176") (name "Net-(U$41--IN)") (class "Default")
      (node (ref "U$41") (pin "3") (pinfunction "-IN_3") (pintype "bidirectional"))
      (node (ref "U$44") (pin "2") (pinfunction "IN-_2") (pintype "bidirectional"))
    )
    (net (code "177") (name "Net-(U$41-GSEN1)") (class "Default")
      (node (ref "R101") (pin "1") (pinfunction "1_1") (pintype "passive"))
      (node (ref "U$41") (pin "4") (pinfunction "GSEN1_4") (pintype "bidirectional"))
      (node (ref "U$41") (pin "5") (pinfunction "GSET1_5") (pintype "bidirectional"))
    )
    (net (code "178") (name "Net-(U$41-GSEN2)") (class "Default")
      (node (ref "R101") (pin "2") (pinfunction "2_2") (pintype "passive"))
      (node (ref "U$41") (pin "12") (pinfunction "GSET2_12") (pintype "bidirectional"))
      (node (ref "U$41") (pin "13") (pinfunction "GSEN2_13") (pintype "bidirectional"))
    )
    (net (code "179") (name "Net-(U$41-IN+)") (class "Default")
      (node (ref "U$41") (pin "14") (pinfunction "IN+_14") (pintype "bidirectional"))
      (node (ref "U$44") (pin "1") (pinfunction "IN+_1") (pintype "bidirectional"))
    )
    (net (code "180") (name "Net-(U$41-OUT)") (class "Default")
      (node (ref "R102") (pin "1") (pinfunction "1_1") (pintype "passive"))
      (node (ref "U$41") (pin "1") (pinfunction "OUT_1") (pintype "bidirectional"))
    )
    (net (code "181") (name "Net-(U$42-INA-)") (class "Default")
      (node (ref "R102") (pin "2") (pinfunction "2_2") (pintype "passive"))
      (node (ref "U$42") (pin "2") (pinfunction "INA-_2") (pintype "bidirectional"))
      (node (ref "U$43") (pin "1") (pinfunction "1_1") (pintype "bidirectional"))
    )
    (net (code "182") (name "Net-(U$42-INB+)") (class "Default")
      (node (ref "C73") (pin "2") (pinfunction "2_2") (pintype "passive"))
      (node (ref "R103") (pin "2") (pinfunction "2_2") (pintype "passive"))
      (node (ref "U$42") (pin "5") (pinfunction "INB+_5") (pintype "bidirectional"))
    )
    (net (code "183") (name "Net-(U$42-INB-)") (class "Default")
      (node (ref "R104") (pin "1") (pinfunction "1_1") (pintype "passive"))
      (node (ref "U$42") (pin "6") (pinfunction "INB-_6") (pintype "bidirectional"))
      (node (ref "U$42") (pin "7") (pinfunction "OUTB_7") (pintype "bidirectional"))
    )
    (net (code "184") (name "Net-(U$42-INC-)") (class "Default")
      (node (ref "R104") (pin "2") (pinfunction "2_2") (pintype "passive"))
      (node (ref "R110") (pin "1") (pinfunction "1_1") (pintype "passive"))
      (node (ref "U$42") (pin "9") (pinfunction "INC-_9") (pintype "bidirectional"))
    )
    (net (code "185") (name "Net-(U$42-IND+)") (class "Default")
      (node (ref "C76") (pin "1") (pinfunction "1_1") (pintype "passive"))
      (node (ref "R106") (pin "1") (pinfunction "1_1") (pintype "passive"))
      (node (ref "U$42") (pin "12") (pinfunction "IND+_12") (pintype "bidirectional"))
    )
    (net (code "186") (name "Net-(U$42-IND-)") (class "Default")
      (node (ref "R108") (pin "1") (pinfunction "1_1") (pintype "passive"))
      (node (ref "R109") (pin "1") (pinfunction "1_1") (pintype "passive"))
      (node (ref "U$42") (pin "13") (pinfunction "IND-_13") (pintype "bidirectional"))
    )
    (net (code "187") (name "Net-(U$42-OUTA)") (class "Default")
      (node (ref "C73") (pin "1") (pinfunction "1_1") (pintype "passive"))
      (node (ref "U$42") (pin "1") (pinfunction "OUTA_1") (pintype "bidirectional"))
      (node (ref "U$43") (pin "2") (pinfunction "2_2") (pintype "bidirectional"))
    )
    (net (code "188") (name "Net-(U$42-OUTD)") (class "Default")
      (node (ref "C77") (pin "2") (pinfunction "2_2") (pintype "passive"))
      (node (ref "R109") (pin "2") (pinfunction "2_2") (pintype "passive"))
      (node (ref "U$42") (pin "14") (pinfunction "OUTD_14") (pintype "bidirectional"))
      (node (ref "U$58") (pin "4") (pinfunction "4_4") (pintype "bidirectional"))
    )
    (net (code "189") (name "Net-(U$45--IN)") (class "Default")
      (node (ref "U$45") (pin "3") (pinfunction "-IN_3") (pintype "bidirectional"))
      (node (ref "U$48") (pin "2") (pinfunction "IN-_2") (pintype "bidirectional"))
    )
    (net (code "190") (name "Net-(U$45-GSEN1)") (class "Default")
      (node (ref "R111") (pin "1") (pinfunction "1_1") (pintype "passive"))
      (node (ref "U$45") (pin "4") (pinfunction "GSEN1_4") (pintype "bidirectional"))
      (node (ref "U$45") (pin "5") (pinfunction "GSET1_5") (pintype "bidirectional"))
    )
    (net (code "191") (name "Net-(U$45-GSEN2)") (class "Default")
      (node (ref "R111") (pin "2") (pinfunction "2_2") (pintype "passive"))
      (node (ref "U$45") (pin "12") (pinfunction "GSET2_12") (pintype "bidirectional"))
      (node (ref "U$45") (pin "13") (pinfunction "GSEN2_13") (pintype "bidirectional"))
    )
    (net (code "192") (name "Net-(U$45-IN+)") (class "Default")
      (node (ref "U$45") (pin "14") (pinfunction "IN+_14") (pintype "bidirectional"))
      (node (ref "U$48") (pin "1") (pinfunction "IN+_1") (pintype "bidirectional"))
    )
    (net (code "193") (name "Net-(U$45-OUT)") (class "Default")
      (node (ref "R112") (pin "1") (pinfunction "1_1") (pintype "passive"))
      (node (ref "U$45") (pin "1") (pinfunction "OUT_1") (pintype "bidirectional"))
    )
    (net (code "194") (name "Net-(U$46-INA-)") (class "Default")
      (node (ref "R112") (pin "2") (pinfunction "2_2") (pintype "passive"))
      (node (ref "U$46") (pin "2") (pinfunction "INA-_2") (pintype "bidirectional"))
      (node (ref "U$47") (pin "1") (pinfunction "1_1") (pintype "bidirectional"))
    )
    (net (code "195") (name "Net-(U$46-INB+)") (class "Default")
      (node (ref "C80") (pin "2") (pinfunction "2_2") (pintype "passive"))
      (node (ref "R113") (pin "2") (pinfunction "2_2") (pintype "passive"))
      (node (ref "U$46") (pin "5") (pinfunction "INB+_5") (pintype "bidirectional"))
    )
    (net (code "196") (name "Net-(U$46-INB-)") (class "Default")
      (node (ref "R114") (pin "1") (pinfunction "1_1") (pintype "passive"))
      (node (ref "U$46") (pin "6") (pinfunction "INB-_6") (pintype "bidirectional"))
      (node (ref "U$46") (pin "7") (pinfunction "OUTB_7") (pintype "bidirectional"))
    )
    (net (code "197") (name "Net-(U$46-INC-)") (class "Default")
      (node (ref "R114") (pin "2") (pinfunction "2_2") (pintype "passive"))
      (node (ref "R120") (pin "1") (pinfunction "1_1") (pintype "passive"))
      (node (ref "U$46") (pin "9") (pinfunction "INC-_9") (pintype "bidirectional"))
    )
    (net (code "198") (name "Net-(U$46-IND+)") (class "Default")
      (node (ref "C83") (pin "1") (pinfunction "1_1") (pintype "passive"))
      (node (ref "R116") (pin "1") (pinfunction "1_1") (pintype "passive"))
      (node (ref "U$46") (pin "12") (pinfunction "IND+_12") (pintype "bidirectional"))
    )
    (net (code "199") (name "Net-(U$46-IND-)") (class "Default")
      (node (ref "R118") (pin "1") (pinfunction "1_1") (pintype "passive"))
      (node (ref "R119") (pin "1") (pinfunction "1_1") (pintype "passive"))
      (node (ref "U$46") (pin "13") (pinfunction "IND-_13") (pintype "bidirectional"))
    )
    (net (code "200") (name "Net-(U$46-OUTA)") (class "Default")
      (node (ref "C80") (pin "1") (pinfunction "1_1") (pintype "passive"))
      (node (ref "U$46") (pin "1") (pinfunction "OUTA_1") (pintype "bidirectional"))
      (node (ref "U$47") (pin "2") (pinfunction "2_2") (pintype "bidirectional"))
    )
    (net (code "201") (name "Net-(U$46-OUTD)") (class "Default")
      (node (ref "C84") (pin "2") (pinfunction "2_2") (pintype "passive"))
      (node (ref "R119") (pin "2") (pinfunction "2_2") (pintype "passive"))
      (node (ref "U$46") (pin "14") (pinfunction "OUTD_14") (pintype "bidirectional"))
      (node (ref "U$58") (pin "3") (pinfunction "3_3") (pintype "bidirectional"))
    )
    (net (code "202") (name "Net-(U$49--IN)") (class "Default")
      (node (ref "U$49") (pin "3") (pinfunction "-IN_3") (pintype "bidirectional"))
      (node (ref "U$52") (pin "2") (pinfunction "IN-_2") (pintype "bidirectional"))
    )
    (net (code "203") (name "Net-(U$49-GSEN1)") (class "Default")
      (node (ref "R121") (pin "1") (pinfunction "1_1") (pintype "passive"))
      (node (ref "U$49") (pin "4") (pinfunction "GSEN1_4") (pintype "bidirectional"))
      (node (ref "U$49") (pin "5") (pinfunction "GSET1_5") (pintype "bidirectional"))
    )
    (net (code "204") (name "Net-(U$49-GSEN2)") (class "Default")
      (node (ref "R121") (pin "2") (pinfunction "2_2") (pintype "passive"))
      (node (ref "U$49") (pin "12") (pinfunction "GSET2_12") (pintype "bidirectional"))
      (node (ref "U$49") (pin "13") (pinfunction "GSEN2_13") (pintype "bidirectional"))
    )
    (net (code "205") (name "Net-(U$49-IN+)") (class "Default")
      (node (ref "U$49") (pin "14") (pinfunction "IN+_14") (pintype "bidirectional"))
      (node (ref "U$52") (pin "1") (pinfunction "IN+_1") (pintype "bidirectional"))
    )
    (net (code "206") (name "Net-(U$49-OUT)") (class "Default")
      (node (ref "R122") (pin "1") (pinfunction "1_1") (pintype "passive"))
      (node (ref "U$49") (pin "1") (pinfunction "OUT_1") (pintype "bidirectional"))
    )
    (net (code "207") (name "Net-(U$50-INA-)") (class "Default")
      (node (ref "R122") (pin "2") (pinfunction "2_2") (pintype "passive"))
      (node (ref "U$50") (pin "2") (pinfunction "INA-_2") (pintype "bidirectional"))
      (node (ref "U$51") (pin "1") (pinfunction "1_1") (pintype "bidirectional"))
    )
    (net (code "208") (name "Net-(U$50-INB+)") (class "Default")
      (node (ref "C87") (pin "2") (pinfunction "2_2") (pintype "passive"))
      (node (ref "R123") (pin "2") (pinfunction "2_2") (pintype "passive"))
      (node (ref "U$50") (pin "5") (pinfunction "INB+_5") (pintype "bidirectional"))
    )
    (net (code "209") (name "Net-(U$50-INB-)") (class "Default")
      (node (ref "R124") (pin "1") (pinfunction "1_1") (pintype "passive"))
      (node (ref "U$50") (pin "6") (pinfunction "INB-_6") (pintype "bidirectional"))
      (node (ref "U$50") (pin "7") (pinfunction "OUTB_7") (pintype "bidirectional"))
    )
    (net (code "210") (name "Net-(U$50-INC-)") (class "Default")
      (node (ref "R124") (pin "2") (pinfunction "2_2") (pintype "passive"))
      (node (ref "R130") (pin "1") (pinfunction "1_1") (pintype "passive"))
      (node (ref "U$50") (pin "9") (pinfunction "INC-_9") (pintype "bidirectional"))
    )
    (net (code "211") (name "Net-(U$50-IND+)") (class "Default")
      (node (ref "C90") (pin "1") (pinfunction "1_1") (pintype "passive"))
      (node (ref "R126") (pin "1") (pinfunction "1_1") (pintype "passive"))
      (node (ref "U$50") (pin "12") (pinfunction "IND+_12") (pintype "bidirectional"))
    )
    (net (code "212") (name "Net-(U$50-IND-)") (class "Default")
      (node (ref "R128") (pin "1") (pinfunction "1_1") (pintype "passive"))
      (node (ref "R129") (pin "1") (pinfunction "1_1") (pintype "passive"))
      (node (ref "U$50") (pin "13") (pinfunction "IND-_13") (pintype "bidirectional"))
    )
    (net (code "213") (name "Net-(U$50-OUTA)") (class "Default")
      (node (ref "C87") (pin "1") (pinfunction "1_1") (pintype "passive"))
      (node (ref "U$50") (pin "1") (pinfunction "OUTA_1") (pintype "bidirectional"))
      (node (ref "U$51") (pin "2") (pinfunction "2_2") (pintype "bidirectional"))
    )
    (net (code "214") (name "Net-(U$50-OUTD)") (class "Default")
      (node (ref "C91") (pin "2") (pinfunction "2_2") (pintype "passive"))
      (node (ref "R129") (pin "2") (pinfunction "2_2") (pintype "passive"))
      (node (ref "U$50") (pin "14") (pinfunction "OUTD_14") (pintype "bidirectional"))
      (node (ref "U$58") (pin "2") (pinfunction "2_2") (pintype "bidirectional"))
    )
    (net (code "215") (name "Net-(U$53--IN)") (class "Default")
      (node (ref "U$53") (pin "3") (pinfunction "-IN_3") (pintype "bidirectional"))
      (node (ref "U$56") (pin "2") (pinfunction "IN-_2") (pintype "bidirectional"))
    )
    (net (code "216") (name "Net-(U$53-GSEN1)") (class "Default")
      (node (ref "R131") (pin "1") (pinfunction "1_1") (pintype "passive"))
      (node (ref "U$53") (pin "4") (pinfunction "GSEN1_4") (pintype "bidirectional"))
      (node (ref "U$53") (pin "5") (pinfunction "GSET1_5") (pintype "bidirectional"))
    )
    (net (code "217") (name "Net-(U$53-GSEN2)") (class "Default")
      (node (ref "R131") (pin "2") (pinfunction "2_2") (pintype "passive"))
      (node (ref "U$53") (pin "12") (pinfunction "GSET2_12") (pintype "bidirectional"))
      (node (ref "U$53") (pin "13") (pinfunction "GSEN2_13") (pintype "bidirectional"))
    )
    (net (code "218") (name "Net-(U$53-IN+)") (class "Default")
      (node (ref "U$53") (pin "14") (pinfunction "IN+_14") (pintype "bidirectional"))
      (node (ref "U$56") (pin "1") (pinfunction "IN+_1") (pintype "bidirectional"))
    )
    (net (code "219") (name "Net-(U$53-OUT)") (class "Default")
      (node (ref "R132") (pin "1") (pinfunction "1_1") (pintype "passive"))
      (node (ref "U$53") (pin "1") (pinfunction "OUT_1") (pintype "bidirectional"))
    )
    (net (code "220") (name "Net-(U$54-INA-)") (class "Default")
      (node (ref "R132") (pin "2") (pinfunction "2_2") (pintype "passive"))
      (node (ref "U$54") (pin "2") (pinfunction "INA-_2") (pintype "bidirectional"))
      (node (ref "U$55") (pin "1") (pinfunction "1_1") (pintype "bidirectional"))
    )
    (net (code "221") (name "Net-(U$54-INB+)") (class "Default")
      (node (ref "C94") (pin "2") (pinfunction "2_2") (pintype "passive"))
      (node (ref "R133") (pin "2") (pinfunction "2_2") (pintype "passive"))
      (node (ref "U$54") (pin "5") (pinfunction "INB+_5") (pintype "bidirectional"))
    )
    (net (code "222") (name "Net-(U$54-INB-)") (class "Default")
      (node (ref "R134") (pin "1") (pinfunction "1_1") (pintype "passive"))
      (node (ref "U$54") (pin "6") (pinfunction "INB-_6") (pintype "bidirectional"))
      (node (ref "U$54") (pin "7") (pinfunction "OUTB_7") (pintype "bidirectional"))
    )
    (net (code "223") (name "Net-(U$54-INC-)") (class "Default")
      (node (ref "R134") (pin "2") (pinfunction "2_2") (pintype "passive"))
      (node (ref "R140") (pin "1") (pinfunction "1_1") (pintype "passive"))
      (node (ref "U$54") (pin "9") (pinfunction "INC-_9") (pintype "bidirectional"))
    )
    (net (code "224") (name "Net-(U$54-IND+)") (class "Default")
      (node (ref "C97") (pin "1") (pinfunction "1_1") (pintype "passive"))
      (node (ref "R136") (pin "1") (pinfunction "1_1") (pintype "passive"))
      (node (ref "U$54") (pin "12") (pinfunction "IND+_12") (pintype "bidirectional"))
    )
    (net (code "225") (name "Net-(U$54-IND-)") (class "Default")
      (node (ref "R138") (pin "1") (pinfunction "1_1") (pintype "passive"))
      (node (ref "R139") (pin "1") (pinfunction "1_1") (pintype "passive"))
      (node (ref "U$54") (pin "13") (pinfunction "IND-_13") (pintype "bidirectional"))
    )
    (net (code "226") (name "Net-(U$54-OUTA)") (class "Default")
      (node (ref "C94") (pin "1") (pinfunction "1_1") (pintype "passive"))
      (node (ref "U$54") (pin "1") (pinfunction "OUTA_1") (pintype "bidirectional"))
      (node (ref "U$55") (pin "2") (pinfunction "2_2") (pintype "bidirectional"))
    )
    (net (code "227") (name "Net-(U$54-OUTD)") (class "Default")
      (node (ref "C98") (pin "2") (pinfunction "2_2") (pintype "passive"))
      (node (ref "R139") (pin "2") (pinfunction "2_2") (pintype "passive"))
      (node (ref "U$54") (pin "14") (pinfunction "OUTD_14") (pintype "bidirectional"))
      (node (ref "U$58") (pin "1") (pinfunction "1_1") (pintype "bidirectional"))
    )
    (net (code "228") (name "unconnected-(U$1-A1OUT-Pad10)") (class "Default")
      (node (ref "U$1") (pin "10") (pinfunction "A1OUT_10") (pintype "bidirectional"))
    )
    (net (code "229") (name "unconnected-(U$1-A2OUT-Pad11)") (class "Default")
      (node (ref "U$1") (pin "11") (pinfunction "A2OUT_11") (pintype "bidirectional"))
    )
    (net (code "230") (name "unconnected-(U$1-COMMON-Pad16)") (class "Default")
      (node (ref "U$1") (pin "16") (pinfunction "COMMON_16") (pintype "bidirectional"))
    )
    (net (code "231") (name "unconnected-(U$1-NC1-Pad8)") (class "Default")
      (node (ref "U$1") (pin "8") (pinfunction "NC1_8") (pintype "bidirectional"))
    )
    (net (code "232") (name "unconnected-(U$1-NC2-Pad9)") (class "Default")
      (node (ref "U$1") (pin "9") (pinfunction "NC2_9") (pintype "bidirectional"))
    )
    (net (code "233") (name "unconnected-(U$1-OFFADJ1-Pad6)") (class "Default")
      (node (ref "U$1") (pin "6") (pinfunction "OFFADJ1_6") (pintype "bidirectional"))
    )
    (net (code "234") (name "unconnected-(U$1-OFFADJ2-Pad7)") (class "Default")
      (node (ref "U$1") (pin "7") (pinfunction "OFFADJ2_7") (pintype "bidirectional"))
    )
    (net (code "235") (name "unconnected-(U$3-Pad3)") (class "Default")
      (node (ref "U$3") (pin "3") (pinfunction "3_3") (pintype "bidirectional"))
    )
    (net (code "236") (name "unconnected-(U$4-A1OUT-Pad10)") (class "Default")
      (node (ref "U$4") (pin "10") (pinfunction "A1OUT_10") (pintype "bidirectional"))
    )
    (net (code "237") (name "unconnected-(U$4-A2OUT-Pad11)") (class "Default")
      (node (ref "U$4") (pin "11") (pinfunction "A2OUT_11") (pintype "bidirectional"))
    )
    (net (code "238") (name "unconnected-(U$4-COMMON-Pad16)") (class "Default")
      (node (ref "U$4") (pin "16") (pinfunction "COMMON_16") (pintype "bidirectional"))
    )
    (net (code "239") (name "unconnected-(U$4-NC1-Pad8)") (class "Default")
      (node (ref "U$4") (pin "8") (pinfunction "NC1_8") (pintype "bidirectional"))
    )
    (net (code "240") (name "unconnected-(U$4-NC2-Pad9)") (class "Default")
      (node (ref "U$4") (pin "9") (pinfunction "NC2_9") (pintype "bidirectional"))
    )
    (net (code "241") (name "unconnected-(U$4-OFFADJ1-Pad6)") (class "Default")
      (node (ref "U$4") (pin "6") (pinfunction "OFFADJ1_6") (pintype "bidirectional"))
    )
    (net (code "242") (name "unconnected-(U$4-OFFADJ2-Pad7)") (class "Default")
      (node (ref "U$4") (pin "7") (pinfunction "OFFADJ2_7") (pintype "bidirectional"))
    )
    (net (code "243") (name "unconnected-(U$6-Pad3)") (class "Default")
      (node (ref "U$6") (pin "3") (pinfunction "3_3") (pintype "bidirectional"))
    )
    (net (code "244") (name "unconnected-(U$8-A1OUT-Pad10)") (class "Default")
      (node (ref "U$8") (pin "10") (pinfunction "A1OUT_10") (pintype "bidirectional"))
    )
    (net (code "245") (name "unconnected-(U$8-A2OUT-Pad11)") (class "Default")
      (node (ref "U$8") (pin "11") (pinfunction "A2OUT_11") (pintype "bidirectional"))
    )
    (net (code "246") (name "unconnected-(U$8-COMMON-Pad16)") (class "Default")
      (node (ref "U$8") (pin "16") (pinfunction "COMMON_16") (pintype "bidirectional"))
    )
    (net (code "247") (name "unconnected-(U$8-NC1-Pad8)") (class "Default")
      (node (ref "U$8") (pin "8") (pinfunction "NC1_8") (pintype "bidirectional"))
    )
    (net (code "248") (name "unconnected-(U$8-NC2-Pad9)") (class "Default")
      (node (ref "U$8") (pin "9") (pinfunction "NC2_9") (pintype "bidirectional"))
    )
    (net (code "249") (name "unconnected-(U$8-OFFADJ1-Pad6)") (class "Default")
      (node (ref "U$8") (pin "6") (pinfunction "OFFADJ1_6") (pintype "bidirectional"))
    )
    (net (code "250") (name "unconnected-(U$8-OFFADJ2-Pad7)") (class "Default")
      (node (ref "U$8") (pin "7") (pinfunction "OFFADJ2_7") (pintype "bidirectional"))
    )
    (net (code "251") (name "unconnected-(U$11-Pad3)") (class "Default")
      (node (ref "U$11") (pin "3") (pinfunction "3_3") (pintype "bidirectional"))
    )
    (net (code "252") (name "unconnected-(U$13-A1OUT-Pad10)") (class "Default")
      (node (ref "U$13") (pin "10") (pinfunction "A1OUT_10") (pintype "bidirectional"))
    )
    (net (code "253") (name "unconnected-(U$13-A2OUT-Pad11)") (class "Default")
      (node (ref "U$13") (pin "11") (pinfunction "A2OUT_11") (pintype "bidirectional"))
    )
    (net (code "254") (name "unconnected-(U$13-COMMON-Pad16)") (class "Default")
      (node (ref "U$13") (pin "16") (pinfunction "COMMON_16") (pintype "bidirectional"))
    )
    (net (code "255") (name "unconnected-(U$13-NC1-Pad8)") (class "Default")
      (node (ref "U$13") (pin "8") (pinfunction "NC1_8") (pintype "bidirectional"))
    )
    (net (code "256") (name "unconnected-(U$13-NC2-Pad9)") (class "Default")
      (node (ref "U$13") (pin "9") (pinfunction "NC2_9") (pintype "bidirectional"))
    )
    (net (code "257") (name "unconnected-(U$13-OFFADJ1-Pad6)") (class "Default")
      (node (ref "U$13") (pin "6") (pinfunction "OFFADJ1_6") (pintype "bidirectional"))
    )
    (net (code "258") (name "unconnected-(U$13-OFFADJ2-Pad7)") (class "Default")
      (node (ref "U$13") (pin "7") (pinfunction "OFFADJ2_7") (pintype "bidirectional"))
    )
    (net (code "259") (name "unconnected-(U$15-Pad3)") (class "Default")
      (node (ref "U$15") (pin "3") (pinfunction "3_3") (pintype "bidirectional"))
    )
    (net (code "260") (name "unconnected-(U$17-A1OUT-Pad10)") (class "Default")
      (node (ref "U$17") (pin "10") (pinfunction "A1OUT_10") (pintype "bidirectional"))
    )
    (net (code "261") (name "unconnected-(U$17-A2OUT-Pad11)") (class "Default")
      (node (ref "U$17") (pin "11") (pinfunction "A2OUT_11") (pintype "bidirectional"))
    )
    (net (code "262") (name "unconnected-(U$17-COMMON-Pad16)") (class "Default")
      (node (ref "U$17") (pin "16") (pinfunction "COMMON_16") (pintype "bidirectional"))
    )
    (net (code "263") (name "unconnected-(U$17-NC1-Pad8)") (class "Default")
      (node (ref "U$17") (pin "8") (pinfunction "NC1_8") (pintype "bidirectional"))
    )
    (net (code "264") (name "unconnected-(U$17-NC2-Pad9)") (class "Default")
      (node (ref "U$17") (pin "9") (pinfunction "NC2_9") (pintype "bidirectional"))
    )
    (net (code "265") (name "unconnected-(U$17-OFFADJ1-Pad6)") (class "Default")
      (node (ref "U$17") (pin "6") (pinfunction "OFFADJ1_6") (pintype "bidirectional"))
    )
    (net (code "266") (name "unconnected-(U$17-OFFADJ2-Pad7)") (class "Default")
      (node (ref "U$17") (pin "7") (pinfunction "OFFADJ2_7") (pintype "bidirectional"))
    )
    (net (code "267") (name "unconnected-(U$19-Pad3)") (class "Default")
      (node (ref "U$19") (pin "3") (pinfunction "3_3") (pintype "bidirectional"))
    )
    (net (code "268") (name "unconnected-(U$21-A1OUT-Pad10)") (class "Default")
      (node (ref "U$21") (pin "10") (pinfunction "A1OUT_10") (pintype "bidirectional"))
    )
    (net (code "269") (name "unconnected-(U$21-A2OUT-Pad11)") (class "Default")
      (node (ref "U$21") (pin "11") (pinfunction "A2OUT_11") (pintype "bidirectional"))
    )
    (net (code "270") (name "unconnected-(U$21-COMMON-Pad16)") (class "Default")
      (node (ref "U$21") (pin "16") (pinfunction "COMMON_16") (pintype "bidirectional"))
    )
    (net (code "271") (name "unconnected-(U$21-NC1-Pad8)") (class "Default")
      (node (ref "U$21") (pin "8") (pinfunction "NC1_8") (pintype "bidirectional"))
    )
    (net (code "272") (name "unconnected-(U$21-NC2-Pad9)") (class "Default")
      (node (ref "U$21") (pin "9") (pinfunction "NC2_9") (pintype "bidirectional"))
    )
    (net (code "273") (name "unconnected-(U$21-OFFADJ1-Pad6)") (class "Default")
      (node (ref "U$21") (pin "6") (pinfunction "OFFADJ1_6") (pintype "bidirectional"))
    )
    (net (code "274") (name "unconnected-(U$21-OFFADJ2-Pad7)") (class "Default")
      (node (ref "U$21") (pin "7") (pinfunction "OFFADJ2_7") (pintype "bidirectional"))
    )
    (net (code "275") (name "unconnected-(U$23-Pad3)") (class "Default")
      (node (ref "U$23") (pin "3") (pinfunction "3_3") (pintype "bidirectional"))
    )
    (net (code "276") (name "unconnected-(U$25-A1OUT-Pad10)") (class "Default")
      (node (ref "U$25") (pin "10") (pinfunction "A1OUT_10") (pintype "bidirectional"))
    )
    (net (code "277") (name "unconnected-(U$25-A2OUT-Pad11)") (class "Default")
      (node (ref "U$25") (pin "11") (pinfunction "A2OUT_11") (pintype "bidirectional"))
    )
    (net (code "278") (name "unconnected-(U$25-COMMON-Pad16)") (class "Default")
      (node (ref "U$25") (pin "16") (pinfunction "COMMON_16") (pintype "bidirectional"))
    )
    (net (code "279") (name "unconnected-(U$25-NC1-Pad8)") (class "Default")
      (node (ref "U$25") (pin "8") (pinfunction "NC1_8") (pintype "bidirectional"))
    )
    (net (code "280") (name "unconnected-(U$25-NC2-Pad9)") (class "Default")
      (node (ref "U$25") (pin "9") (pinfunction "NC2_9") (pintype "bidirectional"))
    )
    (net (code "281") (name "unconnected-(U$25-OFFADJ1-Pad6)") (class "Default")
      (node (ref "U$25") (pin "6") (pinfunction "OFFADJ1_6") (pintype "bidirectional"))
    )
    (net (code "282") (name "unconnected-(U$25-OFFADJ2-Pad7)") (class "Default")
      (node (ref "U$25") (pin "7") (pinfunction "OFFADJ2_7") (pintype "bidirectional"))
    )
    (net (code "283") (name "unconnected-(U$27-Pad3)") (class "Default")
      (node (ref "U$27") (pin "3") (pinfunction "3_3") (pintype "bidirectional"))
    )
    (net (code "284") (name "unconnected-(U$29-A1OUT-Pad10)") (class "Default")
      (node (ref "U$29") (pin "10") (pinfunction "A1OUT_10") (pintype "bidirectional"))
    )
    (net (code "285") (name "unconnected-(U$29-A2OUT-Pad11)") (class "Default")
      (node (ref "U$29") (pin "11") (pinfunction "A2OUT_11") (pintype "bidirectional"))
    )
    (net (code "286") (name "unconnected-(U$29-COMMON-Pad16)") (class "Default")
      (node (ref "U$29") (pin "16") (pinfunction "COMMON_16") (pintype "bidirectional"))
    )
    (net (code "287") (name "unconnected-(U$29-NC1-Pad8)") (class "Default")
      (node (ref "U$29") (pin "8") (pinfunction "NC1_8") (pintype "bidirectional"))
    )
    (net (code "288") (name "unconnected-(U$29-NC2-Pad9)") (class "Default")
      (node (ref "U$29") (pin "9") (pinfunction "NC2_9") (pintype "bidirectional"))
    )
    (net (code "289") (name "unconnected-(U$29-OFFADJ1-Pad6)") (class "Default")
      (node (ref "U$29") (pin "6") (pinfunction "OFFADJ1_6") (pintype "bidirectional"))
    )
    (net (code "290") (name "unconnected-(U$29-OFFADJ2-Pad7)") (class "Default")
      (node (ref "U$29") (pin "7") (pinfunction "OFFADJ2_7") (pintype "bidirectional"))
    )
    (net (code "291") (name "unconnected-(U$31-Pad3)") (class "Default")
      (node (ref "U$31") (pin "3") (pinfunction "3_3") (pintype "bidirectional"))
    )
    (net (code "292") (name "unconnected-(U$33-A1OUT-Pad10)") (class "Default")
      (node (ref "U$33") (pin "10") (pinfunction "A1OUT_10") (pintype "bidirectional"))
    )
    (net (code "293") (name "unconnected-(U$33-A2OUT-Pad11)") (class "Default")
      (node (ref "U$33") (pin "11") (pinfunction "A2OUT_11") (pintype "bidirectional"))
    )
    (net (code "294") (name "unconnected-(U$33-COMMON-Pad16)") (class "Default")
      (node (ref "U$33") (pin "16") (pinfunction "COMMON_16") (pintype "bidirectional"))
    )
    (net (code "295") (name "unconnected-(U$33-NC1-Pad8)") (class "Default")
      (node (ref "U$33") (pin "8") (pinfunction "NC1_8") (pintype "bidirectional"))
    )
    (net (code "296") (name "unconnected-(U$33-NC2-Pad9)") (class "Default")
      (node (ref "U$33") (pin "9") (pinfunction "NC2_9") (pintype "bidirectional"))
    )
    (net (code "297") (name "unconnected-(U$33-OFFADJ1-Pad6)") (class "Default")
      (node (ref "U$33") (pin "6") (pinfunction "OFFADJ1_6") (pintype "bidirectional"))
    )
    (net (code "298") (name "unconnected-(U$33-OFFADJ2-Pad7)") (class "Default")
      (node (ref "U$33") (pin "7") (pinfunction "OFFADJ2_7") (pintype "bidirectional"))
    )
    (net (code "299") (name "unconnected-(U$35-Pad3)") (class "Default")
      (node (ref "U$35") (pin "3") (pinfunction "3_3") (pintype "bidirectional"))
    )
    (net (code "300") (name "unconnected-(U$37-A1OUT-Pad10)") (class "Default")
      (node (ref "U$37") (pin "10") (pinfunction "A1OUT_10") (pintype "bidirectional"))
    )
    (net (code "301") (name "unconnected-(U$37-A2OUT-Pad11)") (class "Default")
      (node (ref "U$37") (pin "11") (pinfunction "A2OUT_11") (pintype "bidirectional"))
    )
    (net (code "302") (name "unconnected-(U$37-COMMON-Pad16)") (class "Default")
      (node (ref "U$37") (pin "16") (pinfunction "COMMON_16") (pintype "bidirectional"))
    )
    (net (code "303") (name "unconnected-(U$37-NC1-Pad8)") (class "Default")
      (node (ref "U$37") (pin "8") (pinfunction "NC1_8") (pintype "bidirectional"))
    )
    (net (code "304") (name "unconnected-(U$37-NC2-Pad9)") (class "Default")
      (node (ref "U$37") (pin "9") (pinfunction "NC2_9") (pintype "bidirectional"))
    )
    (net (code "305") (name "unconnected-(U$37-OFFADJ1-Pad6)") (class "Default")
      (node (ref "U$37") (pin "6") (pinfunction "OFFADJ1_6") (pintype "bidirectional"))
    )
    (net (code "306") (name "unconnected-(U$37-OFFADJ2-Pad7)") (class "Default")
      (node (ref "U$37") (pin "7") (pinfunction "OFFADJ2_7") (pintype "bidirectional"))
    )
    (net (code "307") (name "unconnected-(U$39-Pad3)") (class "Default")
      (node (ref "U$39") (pin "3") (pinfunction "3_3") (pintype "bidirectional"))
    )
    (net (code "308") (name "unconnected-(U$41-A1OUT-Pad10)") (class "Default")
      (node (ref "U$41") (pin "10") (pinfunction "A1OUT_10") (pintype "bidirectional"))
    )
    (net (code "309") (name "unconnected-(U$41-A2OUT-Pad11)") (class "Default")
      (node (ref "U$41") (pin "11") (pinfunction "A2OUT_11") (pintype "bidirectional"))
    )
    (net (code "310") (name "unconnected-(U$41-COMMON-Pad16)") (class "Default")
      (node (ref "U$41") (pin "16") (pinfunction "COMMON_16") (pintype "bidirectional"))
    )
    (net (code "311") (name "unconnected-(U$41-NC1-Pad8)") (class "Default")
      (node (ref "U$41") (pin "8") (pinfunction "NC1_8") (pintype "bidirectional"))
    )
    (net (code "312") (name "unconnected-(U$41-NC2-Pad9)") (class "Default")
      (node (ref "U$41") (pin "9") (pinfunction "NC2_9") (pintype "bidirectional"))
    )
    (net (code "313") (name "unconnected-(U$41-OFFADJ1-Pad6)") (class "Default")
      (node (ref "U$41") (pin "6") (pinfunction "OFFADJ1_6") (pintype "bidirectional"))
    )
    (net (code "314") (name "unconnected-(U$41-OFFADJ2-Pad7)") (class "Default")
      (node (ref "U$41") (pin "7") (pinfunction "OFFADJ2_7") (pintype "bidirectional"))
    )
    (net (code "315") (name "unconnected-(U$43-Pad3)") (class "Default")
      (node (ref "U$43") (pin "3") (pinfunction "3_3") (pintype "bidirectional"))
    )
    (net (code "316") (name "unconnected-(U$45-A1OUT-Pad10)") (class "Default")
      (node (ref "U$45") (pin "10") (pinfunction "A1OUT_10") (pintype "bidirectional"))
    )
    (net (code "317") (name "unconnected-(U$45-A2OUT-Pad11)") (class "Default")
      (node (ref "U$45") (pin "11") (pinfunction "A2OUT_11") (pintype "bidirectional"))
    )
    (net (code "318") (name "unconnected-(U$45-COMMON-Pad16)") (class "Default")
      (node (ref "U$45") (pin "16") (pinfunction "COMMON_16") (pintype "bidirectional"))
    )
    (net (code "319") (name "unconnected-(U$45-NC1-Pad8)") (class "Default")
      (node (ref "U$45") (pin "8") (pinfunction "NC1_8") (pintype "bidirectional"))
    )
    (net (code "320") (name "unconnected-(U$45-NC2-Pad9)") (class "Default")
      (node (ref "U$45") (pin "9") (pinfunction "NC2_9") (pintype "bidirectional"))
    )
    (net (code "321") (name "unconnected-(U$45-OFFADJ1-Pad6)") (class "Default")
      (node (ref "U$45") (pin "6") (pinfunction "OFFADJ1_6") (pintype "bidirectional"))
    )
    (net (code "322") (name "unconnected-(U$45-OFFADJ2-Pad7)") (class "Default")
      (node (ref "U$45") (pin "7") (pinfunction "OFFADJ2_7") (pintype "bidirectional"))
    )
    (net (code "323") (name "unconnected-(U$47-Pad3)") (class "Default")
      (node (ref "U$47") (pin "3") (pinfunction "3_3") (pintype "bidirectional"))
    )
    (net (code "324") (name "unconnected-(U$49-A1OUT-Pad10)") (class "Default")
      (node (ref "U$49") (pin "10") (pinfunction "A1OUT_10") (pintype "bidirectional"))
    )
    (net (code "325") (name "unconnected-(U$49-A2OUT-Pad11)") (class "Default")
      (node (ref "U$49") (pin "11") (pinfunction "A2OUT_11") (pintype "bidirectional"))
    )
    (net (code "326") (name "unconnected-(U$49-COMMON-Pad16)") (class "Default")
      (node (ref "U$49") (pin "16") (pinfunction "COMMON_16") (pintype "bidirectional"))
    )
    (net (code "327") (name "unconnected-(U$49-NC1-Pad8)") (class "Default")
      (node (ref "U$49") (pin "8") (pinfunction "NC1_8") (pintype "bidirectional"))
    )
    (net (code "328") (name "unconnected-(U$49-NC2-Pad9)") (class "Default")
      (node (ref "U$49") (pin "9") (pinfunction "NC2_9") (pintype "bidirectional"))
    )
    (net (code "329") (name "unconnected-(U$49-OFFADJ1-Pad6)") (class "Default")
      (node (ref "U$49") (pin "6") (pinfunction "OFFADJ1_6") (pintype "bidirectional"))
    )
    (net (code "330") (name "unconnected-(U$49-OFFADJ2-Pad7)") (class "Default")
      (node (ref "U$49") (pin "7") (pinfunction "OFFADJ2_7") (pintype "bidirectional"))
    )
    (net (code "331") (name "unconnected-(U$51-Pad3)") (class "Default")
      (node (ref "U$51") (pin "3") (pinfunction "3_3") (pintype "bidirectional"))
    )
    (net (code "332") (name "unconnected-(U$53-A1OUT-Pad10)") (class "Default")
      (node (ref "U$53") (pin "10") (pinfunction "A1OUT_10") (pintype "bidirectional"))
    )
    (net (code "333") (name "unconnected-(U$53-A2OUT-Pad11)") (class "Default")
      (node (ref "U$53") (pin "11") (pinfunction "A2OUT_11") (pintype "bidirectional"))
    )
    (net (code "334") (name "unconnected-(U$53-COMMON-Pad16)") (class "Default")
      (node (ref "U$53") (pin "16") (pinfunction "COMMON_16") (pintype "bidirectional"))
    )
    (net (code "335") (name "unconnected-(U$53-NC1-Pad8)") (class "Default")
      (node (ref "U$53") (pin "8") (pinfunction "NC1_8") (pintype "bidirectional"))
    )
    (net (code "336") (name "unconnected-(U$53-NC2-Pad9)") (class "Default")
      (node (ref "U$53") (pin "9") (pinfunction "NC2_9") (pintype "bidirectional"))
    )
    (net (code "337") (name "unconnected-(U$53-OFFADJ1-Pad6)") (class "Default")
      (node (ref "U$53") (pin "6") (pinfunction "OFFADJ1_6") (pintype "bidirectional"))
    )
    (net (code "338") (name "unconnected-(U$53-OFFADJ2-Pad7)") (class "Default")
      (node (ref "U$53") (pin "7") (pinfunction "OFFADJ2_7") (pintype "bidirectional"))
    )
    (net (code "339") (name "unconnected-(U$55-Pad3)") (class "Default")
      (node (ref "U$55") (pin "3") (pinfunction "3_3") (pintype "bidirectional"))
    )
  )
)
